# SCH___2021-06-06.net
KiCad netlist of a schematic drawn in EasyEDA
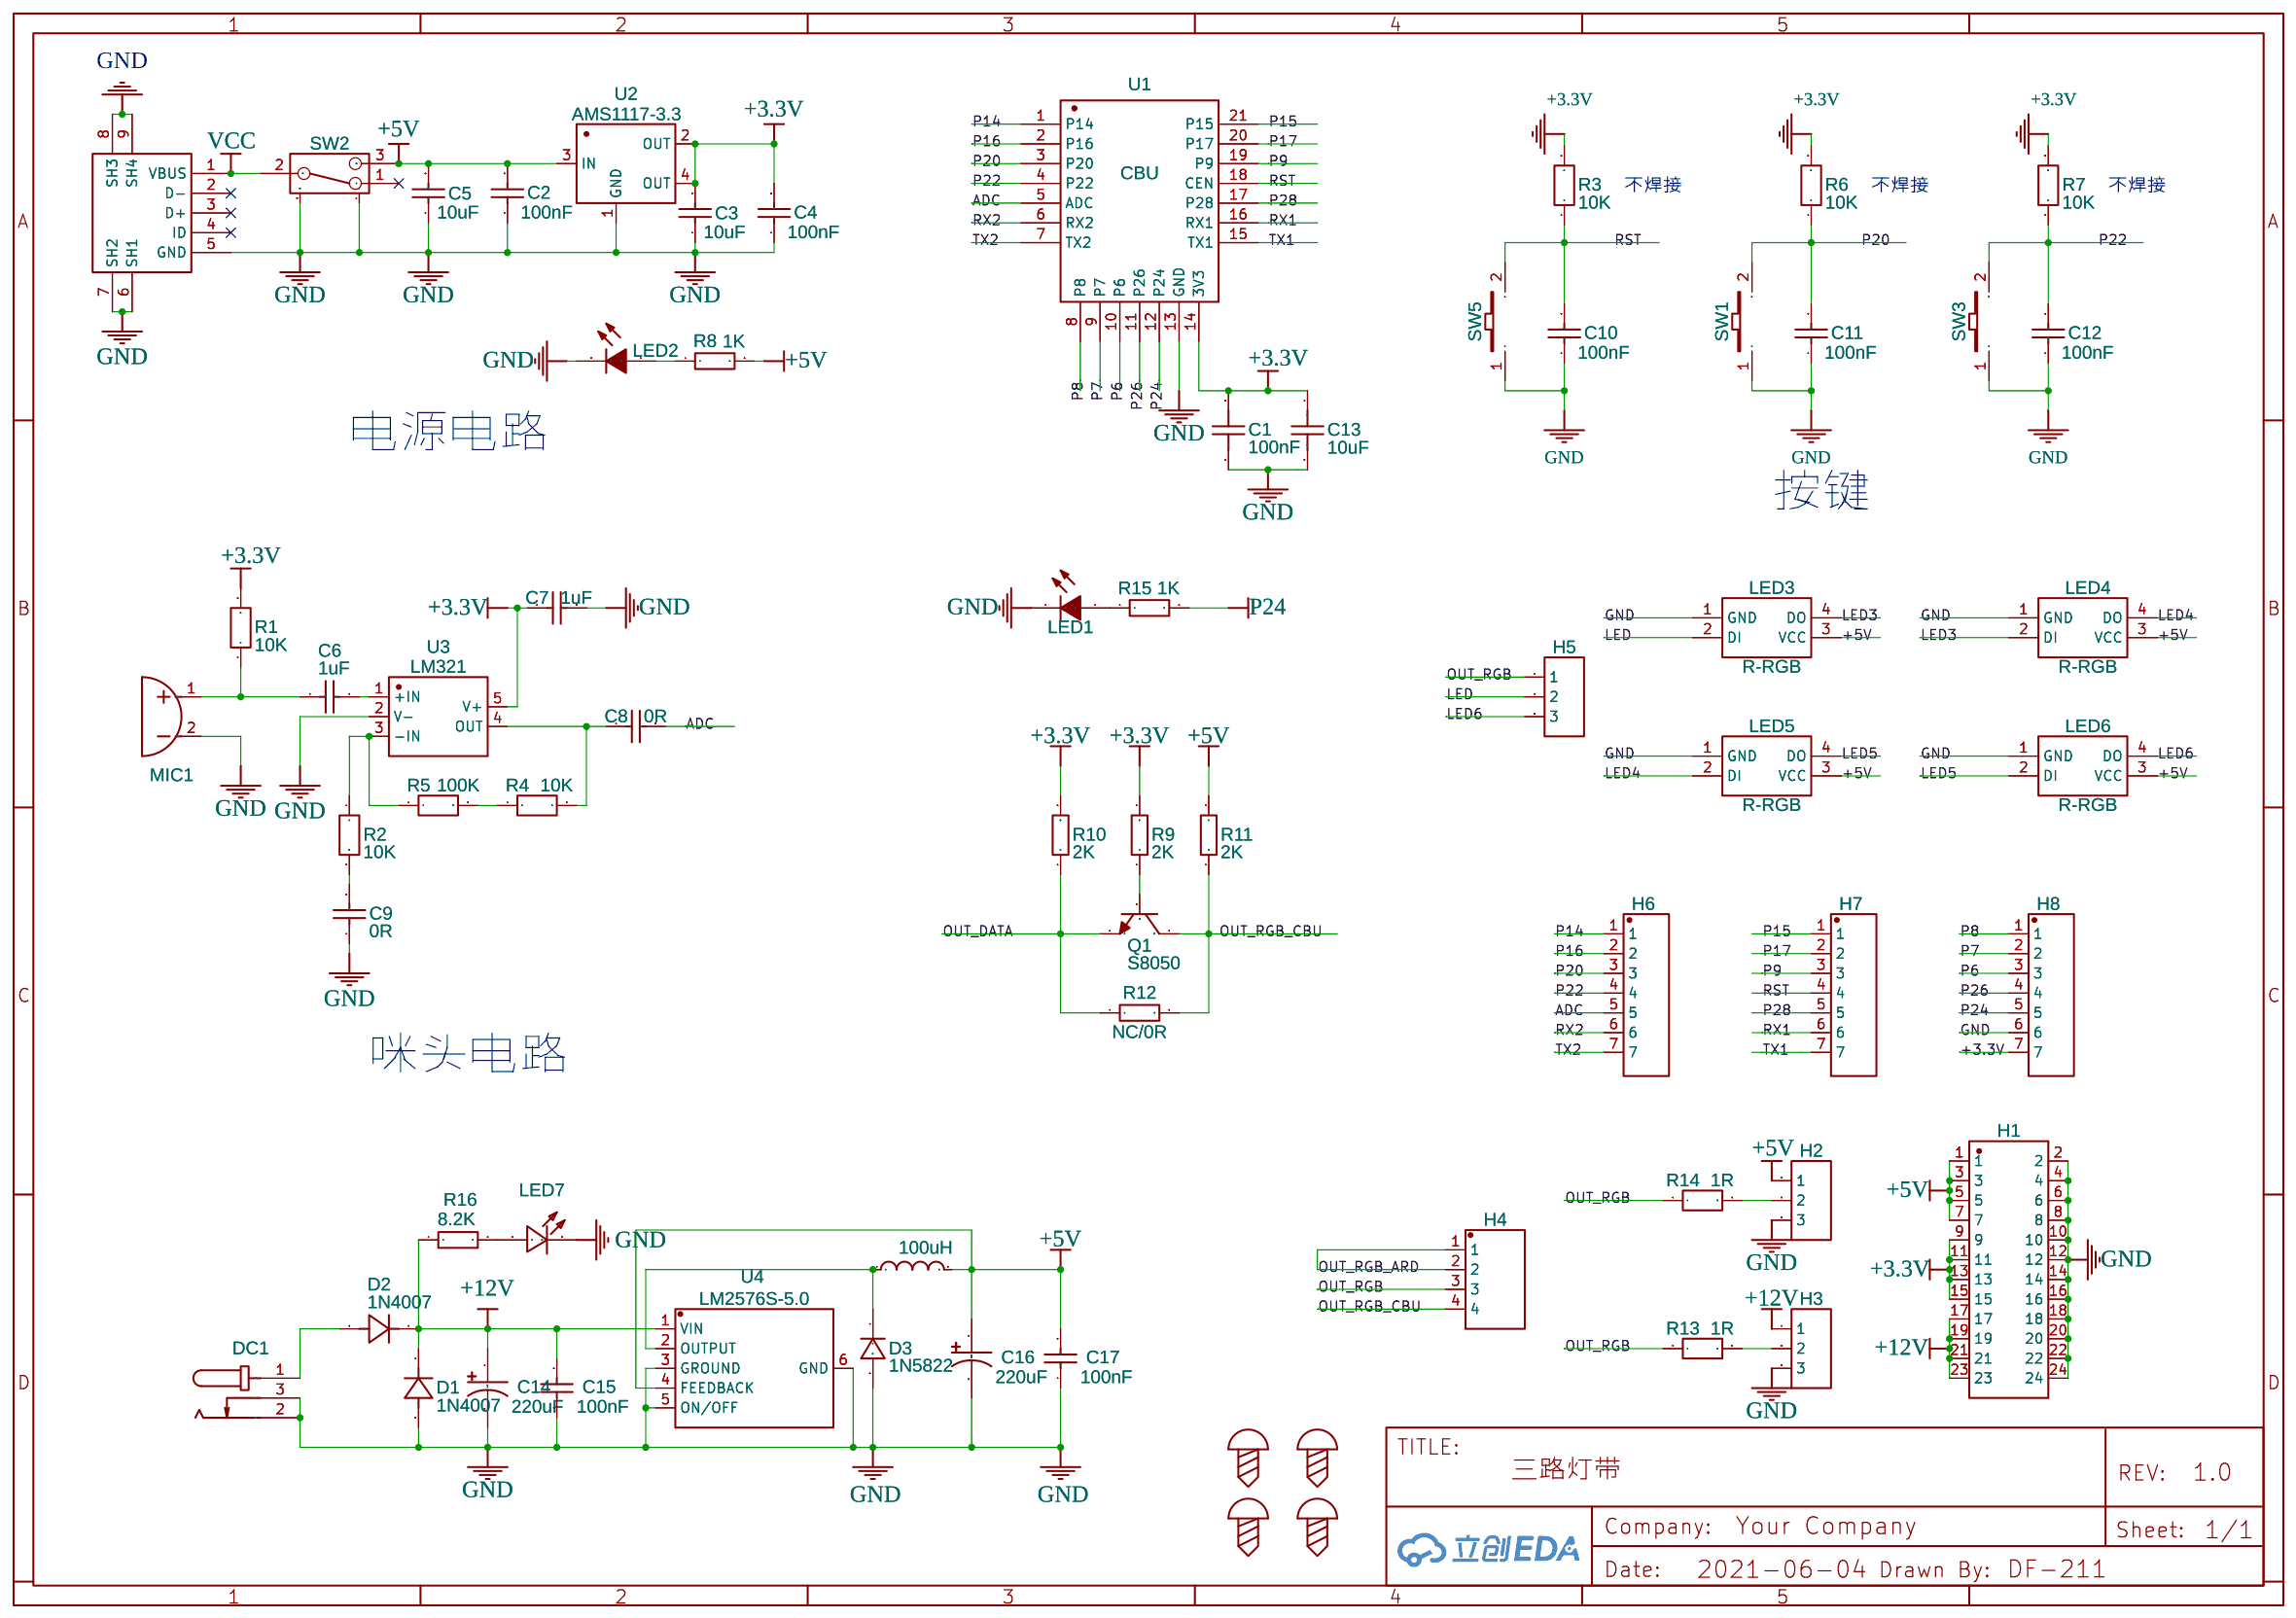
[diagram p0: 原理图]
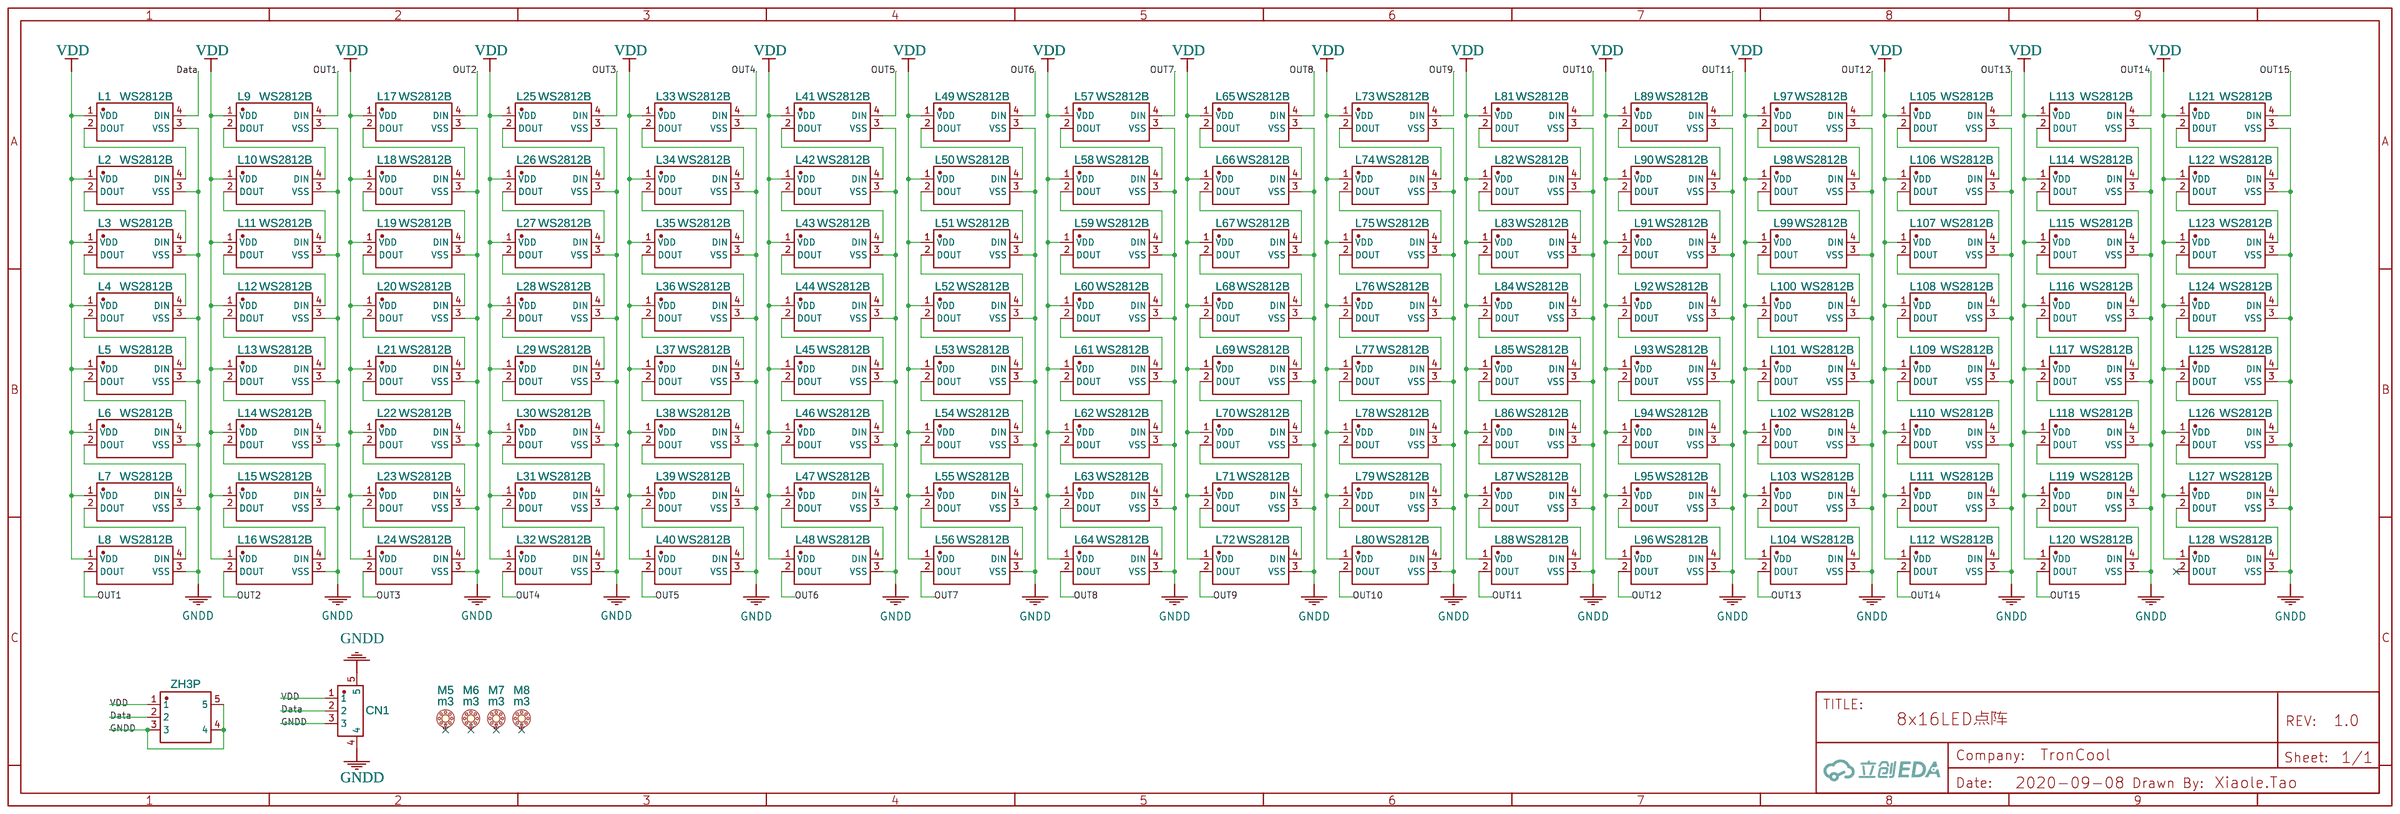
[diagram p1: WS2812灯带]

(export (version "E")
  (design (tool "Eeschema 10.0.6"))
  (components
    (comp (ref "C1")
      (value "100nF")
      (fields
        (field (name "BOM_Manufacturer Part") "CC0603KRX7R9BB104")
        (field (name "BOM_Supplier Part") "C14663")
      )
      (libsource (lib "") (part "CC0603KRX7R9BB104"))
    )
    (comp (ref "C2")
      (value "100nF")
      (fields
        (field (name "BOM_Manufacturer Part") "0805B104K500NT")
        (field (name "BOM_Supplier Part") "C38141")
      )
      (libsource (lib "") (part "0805B104K500NT"))
    )
    (comp (ref "C3")
      (value "10uF")
      (fields
        (field (name "BOM_Manufacturer Part") "CL21A106KOQNNNE")
        (field (name "BOM_Supplier Part") "C1713")
      )
      (libsource (lib "") (part "CL21A106KOQNNNE"))
    )
    (comp (ref "C4")
      (value "100nF")
      (fields
        (field (name "BOM_Manufacturer Part") "0805B104K500NT")
        (field (name "BOM_Supplier Part") "C38141")
      )
      (libsource (lib "") (part "0805B104K500NT"))
    )
    (comp (ref "C5")
      (value "10uF")
      (fields
        (field (name "BOM_Manufacturer Part") "CL21A106KOQNNNE")
        (field (name "BOM_Supplier Part") "C1713")
      )
      (libsource (lib "") (part "CL21A106KOQNNNE"))
    )
    (comp (ref "C6")
      (value "1uF")
      (fields
        (field (name "BOM_Manufacturer Part") "CL21F105ZAFNNNE")
        (field (name "BOM_Supplier Part") "C1761")
      )
      (libsource (lib "") (part "CL21F105ZAFNNNE"))
    )
    (comp (ref "C7")
      (value "1uF")
      (fields
        (field (name "BOM_Manufacturer Part") "CL21F105ZAFNNNE")
        (field (name "BOM_Supplier Part") "C1761")
      )
      (libsource (lib "") (part "CL21F105ZAFNNNE"))
    )
    (comp (ref "C8")
      (value "0R")
      (fields
        (field (name "BOM_Manufacturer Part") "CL21F105ZAFNNNE")
        (field (name "BOM_Supplier Part") "C1761")
      )
      (libsource (lib "") (part "CL21F105ZAFNNNE"))
    )
    (comp (ref "C9")
      (value "0R")
      (fields
        (field (name "BOM_Manufacturer Part") "CL21F105ZAFNNNE")
        (field (name "BOM_Supplier Part") "C1761")
      )
      (libsource (lib "") (part "CL21F105ZAFNNNE_1"))
    )
    (comp (ref "C10")
      (value "100nF")
      (fields
        (field (name "BOM_Manufacturer Part") "0805B104K500NT")
        (field (name "BOM_Supplier Part") "C38141")
      )
      (libsource (lib "") (part "0805B104K500NT"))
    )
    (comp (ref "C11")
      (value "100nF")
      (fields
        (field (name "BOM_Manufacturer Part") "0805B104K500NT")
        (field (name "BOM_Supplier Part") "C38141")
      )
      (libsource (lib "") (part "0805B104K500NT"))
    )
    (comp (ref "C12")
      (value "100nF")
      (fields
        (field (name "BOM_Manufacturer Part") "0805B104K500NT")
        (field (name "BOM_Supplier Part") "C38141")
      )
      (libsource (lib "") (part "0805B104K500NT"))
    )
    (comp (ref "C13")
      (value "10uF")
      (fields
        (field (name "BOM_Manufacturer Part") "JMK212AB7106KGHT")
        (field (name "BOM_Supplier Part") "C386019")
      )
      (libsource (lib "") (part "JMK212AB7106KGHT"))
    )
    (comp (ref "C14")
      (value "220uF")
      (fields
        (field (name "BOM_Manufacturer Part") "EEEFC1E221AP")
        (field (name "BOM_Supplier Part") "C178520")
      )
      (libsource (lib "") (part "EEEFC1E221AP"))
    )
    (comp (ref "C15")
      (value "100nF")
      (fields
        (field (name "BOM_Manufacturer Part") "CL21F104ZBCNNNC")
        (field (name "BOM_Supplier Part") "C1760")
      )
      (libsource (lib "") (part "CL21F104ZBCNNNC"))
    )
    (comp (ref "C16")
      (value "220uF")
      (fields
        (field (name "BOM_Manufacturer Part") "EEEFC1E221AP")
        (field (name "BOM_Supplier Part") "C178520")
      )
      (libsource (lib "") (part "EEEFC1E221AP_1"))
    )
    (comp (ref "C17")
      (value "100nF")
      (fields
        (field (name "BOM_Manufacturer Part") "CL10F104ZB8NNNC")
        (field (name "BOM_Supplier Part") "C1688")
      )
      (libsource (lib "") (part "CL10F104ZB8NNNC"))
    )
    (comp (ref "D1")
      (value "1N4007")
      (fields (field (name "BOM_Supplier Part") "C727081"))
      (libsource (lib "") (part "1N4007_C727081"))
    )
    (comp (ref "D2")
      (value "1N4007")
      (fields (field (name "BOM_Supplier Part") "C727081"))
      (libsource (lib "") (part "1N4007_C727081_1"))
    )
    (comp (ref "D3")
      (value "1N5822")
      (fields
        (field (name "BOM_Manufacturer Part") "SS36F-SMAF")
        (field (name "BOM_Supplier Part") "C364271")
      )
      (libsource (lib "") (part "1N5822-SMA"))
    )
    (comp (ref "DC1")
      (value "DC-005A-20A")
      (fields (field (name "BOM_Supplier Part") "C362144"))
      (libsource (lib "") (part "DC-005A-20A"))
    )
    (comp (ref "H1")
      (value "A2541HWV-2X12P")
      (fields
        (field (name "BOM_Manufacturer Part") "A2541HWV-2x12P")
        (field (name "BOM_Supplier Part") "C239352")
      )
      (libsource (lib "") (part "A2541HWV-2X12P"))
    )
    (comp (ref "H2")
      (value "Header-Male-2.54_1x3")
      (fields
        (field (name "BOM_Manufacturer Part") "Header2.54mm 1*3P")
        (field (name "BOM_Supplier Part") "C49257")
      )
      (libsource (lib "") (part "Header-Male-2.54_1x3"))
    )
    (comp (ref "H3")
      (value "Header-Male-2.54_1x3")
      (fields
        (field (name "BOM_Manufacturer Part") "Header2.54mm 1*3P")
        (field (name "BOM_Supplier Part") "C49257")
      )
      (libsource (lib "") (part "Header-Male-2.54_1x3"))
    )
    (comp (ref "H4")
      (value "MTP125-1104S1")
      (fields (field (name "BOM_Supplier Part") "C358686"))
      (libsource (lib "") (part "MTP125-1104S1"))
    )
    (comp (ref "H5")
      (value "Header-Male-2.54_1x3")
      (fields
        (field (name "BOM_Manufacturer Part") "Header2.54mm 1*3P")
        (field (name "BOM_Supplier Part") "C49257")
      )
      (libsource (lib "") (part "Header-Male-2.54_1x3"))
    )
    (comp (ref "H6")
      (value "220S-1*7P H=8.5MM Ytype Gold-plated")
      (fields (field (name "BOM_Supplier Part") "C124418"))
      (libsource (lib "") (part "220S-1*7P H=8.5MM Ytype Gold-plated"))
    )
    (comp (ref "H7")
      (value "220S-1*7P H=8.5MM Ytype Gold-plated")
      (fields (field (name "BOM_Supplier Part") "C124418"))
      (libsource (lib "") (part "220S-1*7P H=8.5MM Ytype Gold-plated"))
    )
    (comp (ref "H8")
      (value "220S-1*7P H=8.5MM Ytype Gold-plated")
      (fields (field (name "BOM_Supplier Part") "C124418"))
      (libsource (lib "") (part "220S-1*7P H=8.5MM Ytype Gold-plated"))
    )
    (comp (ref "LED1")
      (value "19-217/BHC-ZL1M2RY/3T")
      (fields (field (name "BOM_Supplier Part") "C72041"))
      (libsource (lib "") (part "19-217/BHC-ZL1M2RY/3T"))
    )
    (comp (ref "LED2")
      (value "19-217/BHC-ZL1M2RY/3T")
      (fields (field (name "BOM_Supplier Part") "C72041"))
      (libsource (lib "") (part "19-217/BHC-ZL1M2RY/3T"))
    )
    (comp (ref "LED3")
      (value "R-RGB")
      (fields (field (name "BOM_Manufacturer Part") "WS2812B-B") (field (name "BOM_Supplier Part") "C114586"))
      (libsource (lib "") (part "R-RGB"))
    )
    (comp (ref "LED4")
      (value "R-RGB")
      (fields (field (name "BOM_Manufacturer Part") "WS2812B-B") (field (name "BOM_Supplier Part") "C114586"))
      (libsource (lib "") (part "R-RGB"))
    )
    (comp (ref "LED5")
      (value "R-RGB")
      (fields (field (name "BOM_Manufacturer Part") "WS2812B-B") (field (name "BOM_Supplier Part") "C114586"))
      (libsource (lib "") (part "R-RGB"))
    )
    (comp (ref "LED6")
      (value "R-RGB")
      (fields (field (name "BOM_Manufacturer Part") "WS2812B-B") (field (name "BOM_Supplier Part") "C114586"))
      (libsource (lib "") (part "R-RGB"))
    )
    (comp (ref "LED7")
      (value "ORH-G35A")
      (fields (field (name "BOM_Supplier Part") "C205442"))
      (libsource (lib "") (part "ORH-G35A"))
    )
    (comp (ref "LL1")
      (value "100uH")
      (fields
        (field (name "BOM_Manufacturer Part") "GCRH125-101MC")
        (field (name "BOM_Supplier Part") "C439399")
      )
      (libsource (lib "") (part "GCRH125-101MC"))
    )
    (comp (ref "MIC1")
      (value "GMI9767P-36DB")
      (fields (field (name "BOM_Supplier Part") "C234015"))
      (libsource (lib "") (part "GMI9767P-36DB"))
    )
    (comp (ref "Q1")
      (value "S8050")
      (fields (field (name "BOM_Supplier Part") "C908252"))
      (libsource (lib "") (part "S8050_C908252"))
    )
    (comp (ref "R1")
      (value "10K")
      (fields
        (field (name "BOM_Manufacturer Part") "RT0805WRD0710KL")
        (field (name "BOM_Supplier Part") "C706400")
      )
      (libsource (lib "") (part "RT0805WRD0710KL"))
    )
    (comp (ref "R2")
      (value "10K")
      (fields
        (field (name "BOM_Manufacturer Part") "RT0805WRD0710KL")
        (field (name "BOM_Supplier Part") "C706400")
      )
      (libsource (lib "") (part "RT0805WRD0710KL_2"))
    )
    (comp (ref "R3")
      (value "10K")
      (fields
        (field (name "BOM_Manufacturer Part") "RT0805WRD0710KL")
        (field (name "BOM_Supplier Part") "C706400")
      )
      (libsource (lib "") (part "RT0805WRD0710KL"))
    )
    (comp (ref "R4")
      (value "10K")
      (fields
        (field (name "BOM_Manufacturer Part") "RT0805WRD0710KL")
        (field (name "BOM_Supplier Part") "C706400")
      )
      (libsource (lib "") (part "RT0805WRD0710KL_1"))
    )
    (comp (ref "R5")
      (value "100K")
      (fields
        (field (name "BOM_Manufacturer Part") "CRCW0805100KFKEA")
        (field (name "BOM_Supplier Part") "C844935")
      )
      (libsource (lib "") (part "CRCW0805100KFKEA"))
    )
    (comp (ref "R6")
      (value "10K")
      (fields
        (field (name "BOM_Manufacturer Part") "RT0805WRD0710KL")
        (field (name "BOM_Supplier Part") "C706400")
      )
      (libsource (lib "") (part "RT0805WRD0710KL"))
    )
    (comp (ref "R7")
      (value "10K")
      (fields
        (field (name "BOM_Manufacturer Part") "RT0805WRD0710KL")
        (field (name "BOM_Supplier Part") "C706400")
      )
      (libsource (lib "") (part "RT0805WRD0710KL"))
    )
    (comp (ref "R8")
      (value "1K")
      (fields
        (field (name "BOM_Manufacturer Part") "0805W8F1001T5E")
        (field (name "BOM_Supplier Part") "C17513")
      )
      (libsource (lib "") (part "0805W8F1001T5E"))
    )
    (comp (ref "R9")
      (value "2K")
      (fields
        (field (name "BOM_Manufacturer Part") "RMC08052K5%N")
        (field (name "BOM_Supplier Part") "C269731")
      )
      (libsource (lib "") (part "RMC08052K5%N"))
    )
    (comp (ref "R10")
      (value "2K")
      (fields
        (field (name "BOM_Manufacturer Part") "RMC08052K5%N")
        (field (name "BOM_Supplier Part") "C269731")
      )
      (libsource (lib "") (part "RMC08052K5%N"))
    )
    (comp (ref "R11")
      (value "2K")
      (fields
        (field (name "BOM_Manufacturer Part") "RMC08052K5%N")
        (field (name "BOM_Supplier Part") "C269731")
      )
      (libsource (lib "") (part "RMC08052K5%N"))
    )
    (comp (ref "R12")
      (value "NC/0R")
      (fields
        (field (name "BOM_Manufacturer Part") "0805W8J0000T5E")
        (field (name "BOM_Supplier Part") "C25275")
      )
      (libsource (lib "") (part "0805W8J0000T5E"))
    )
    (comp (ref "R13")
      (value "1R")
      (fields
        (field (name "BOM_Manufacturer Part") "AC0805DR-071RL")
        (field (name "BOM_Supplier Part") "C727972")
      )
      (libsource (lib "") (part "AC0805DR-071RL"))
    )
    (comp (ref "R14")
      (value "1R")
      (fields
        (field (name "BOM_Manufacturer Part") "AC0805DR-071RL")
        (field (name "BOM_Supplier Part") "C727972")
      )
      (libsource (lib "") (part "AC0805DR-071RL"))
    )
    (comp (ref "R15")
      (value "1K")
      (fields
        (field (name "BOM_Manufacturer Part") "0805W8F1001T5E")
        (field (name "BOM_Supplier Part") "C17513")
      )
      (libsource (lib "") (part "0805W8F1001T5E"))
    )
    (comp (ref "R16")
      (value "8.2K")
      (fields
        (field (name "BOM_Manufacturer Part") "0805W8J0822T5E")
        (field (name "BOM_Supplier Part") "C26028")
      )
      (libsource (lib "") (part "0805W8J0822T5E"))
    )
    (comp (ref "SW1")
      (value "S2")
      (fields
        (field (name "BOM_Manufacturer Part") "K2-1107ST-A4SW-06")
        (field (name "BOM_Supplier Part") "C118141")
      )
      (libsource (lib "") (part "Unknown_880_-650"))
    )
    (comp (ref "SW2")
      (value "SS-12D02-VG4")
      (fields (field (name "BOM_Supplier Part") "C136719"))
      (libsource (lib "") (part "SS-12D02-VG4"))
    )
    (comp (ref "SW3")
      (value "S2")
      (fields
        (field (name "BOM_Manufacturer Part") "K2-1107ST-A4SW-06")
        (field (name "BOM_Supplier Part") "C118141")
      )
      (libsource (lib "") (part "Unknown_1000_-650"))
    )
    (comp (ref "SW5")
      (value "S2")
      (fields
        (field (name "BOM_Manufacturer Part") "K2-1107ST-A4SW-06")
        (field (name "BOM_Supplier Part") "C118141")
      )
      (libsource (lib "") (part "Unknown_755_-650"))
    )
    (comp (ref "TP1") (value "M3铜柱") (libsource (lib "") (part "M3铜柱")))
    (comp (ref "TP2") (value "M3铜柱") (libsource (lib "") (part "M3铜柱")))
    (comp (ref "TP3") (value "M3铜柱") (libsource (lib "") (part "M3铜柱")))
    (comp (ref "TP4") (value "M3铜柱") (libsource (lib "") (part "M3铜柱")))
    (comp (ref "U1") (value "CBU") (libsource (lib "") (part "模块-CBU")))
    (comp (ref "U2")
      (value "AMS1117-3.3")
      (fields (field (name "BOM_Supplier Part") "C498117"))
      (libsource (lib "") (part "AMS1117-3.3"))
    )
    (comp (ref "U3")
      (value "LM321")
      (fields (field (name "BOM_Supplier Part") "C686636"))
      (libsource (lib "") (part "LM321"))
    )
    (comp (ref "U4")
      (value "LM2576S-5.0")
      (fields
        (field (name "BOM_Manufacturer Part") "LM2576S-5.0/TR")
        (field (name "BOM_Supplier Part") "C340927")
      )
      (libsource (lib "") (part "LM2576S-5.0/TR_C340927"))
    )
    (comp (ref "USB")
      (value "MICROXNJ")
      (fields (field (name "BOM_Manufacturer Part") "MicroXNJ") (field (name "BOM_Supplier Part") "C404969"))
      (libsource (lib "") (part "MICROXNJ"))
    )
    (comp (ref "CN1")
      (value "2.54-3P WT")
      (fields (field (name "BOM_Supplier Part") "C2681546"))
      (libsource (lib "") (part "2.54-3P WT"))
    )
    (comp (ref "CN6")
      (value "ZH3P")
      (fields (field (name "BOM_Supplier Part") "C145991"))
      (libsource (lib "") (part "ZH1.5-3P SMD"))
    )
    (comp (ref "L1")
      (value "WS2812B")
      (fields
        (field (name "BOM_Manufacturer Part") "WS2812B-Mini")
        (field (name "BOM_Supplier Part") "C527089")
      )
      (libsource (lib "") (part "WS2812B-MINI"))
    )
    (comp (ref "L2")
      (value "WS2812B")
      (fields
        (field (name "BOM_Manufacturer Part") "WS2812B-Mini")
        (field (name "BOM_Supplier Part") "C527089")
      )
      (libsource (lib "") (part "WS2812B-MINI"))
    )
    (comp (ref "L3")
      (value "WS2812B")
      (fields
        (field (name "BOM_Manufacturer Part") "WS2812B-Mini")
        (field (name "BOM_Supplier Part") "C527089")
      )
      (libsource (lib "") (part "WS2812B-MINI"))
    )
    (comp (ref "L4")
      (value "WS2812B")
      (fields
        (field (name "BOM_Manufacturer Part") "WS2812B-Mini")
        (field (name "BOM_Supplier Part") "C527089")
      )
      (libsource (lib "") (part "WS2812B-MINI"))
    )
    (comp (ref "L5")
      (value "WS2812B")
      (fields
        (field (name "BOM_Manufacturer Part") "WS2812B-Mini")
        (field (name "BOM_Supplier Part") "C527089")
      )
      (libsource (lib "") (part "WS2812B-MINI"))
    )
    (comp (ref "L6")
      (value "WS2812B")
      (fields
        (field (name "BOM_Manufacturer Part") "WS2812B-Mini")
        (field (name "BOM_Supplier Part") "C527089")
      )
      (libsource (lib "") (part "WS2812B-MINI"))
    )
    (comp (ref "L7")
      (value "WS2812B")
      (fields
        (field (name "BOM_Manufacturer Part") "WS2812B-Mini")
        (field (name "BOM_Supplier Part") "C527089")
      )
      (libsource (lib "") (part "WS2812B-MINI"))
    )
    (comp (ref "L8")
      (value "WS2812B")
      (fields
        (field (name "BOM_Manufacturer Part") "WS2812B-Mini")
        (field (name "BOM_Supplier Part") "C527089")
      )
      (libsource (lib "") (part "WS2812B-MINI"))
    )
    (comp (ref "L9")
      (value "WS2812B")
      (fields
        (field (name "BOM_Manufacturer Part") "WS2812B-Mini")
        (field (name "BOM_Supplier Part") "C527089")
      )
      (libsource (lib "") (part "WS2812B-MINI"))
    )
    (comp (ref "L10")
      (value "WS2812B")
      (fields
        (field (name "BOM_Manufacturer Part") "WS2812B-Mini")
        (field (name "BOM_Supplier Part") "C527089")
      )
      (libsource (lib "") (part "WS2812B-MINI"))
    )
    (comp (ref "L11")
      (value "WS2812B")
      (fields
        (field (name "BOM_Manufacturer Part") "WS2812B-Mini")
        (field (name "BOM_Supplier Part") "C527089")
      )
      (libsource (lib "") (part "WS2812B-MINI"))
    )
    (comp (ref "L12")
      (value "WS2812B")
      (fields
        (field (name "BOM_Manufacturer Part") "WS2812B-Mini")
        (field (name "BOM_Supplier Part") "C527089")
      )
      (libsource (lib "") (part "WS2812B-MINI"))
    )
    (comp (ref "L13")
      (value "WS2812B")
      (fields
        (field (name "BOM_Manufacturer Part") "WS2812B-Mini")
        (field (name "BOM_Supplier Part") "C527089")
      )
      (libsource (lib "") (part "WS2812B-MINI"))
    )
    (comp (ref "L14")
      (value "WS2812B")
      (fields
        (field (name "BOM_Manufacturer Part") "WS2812B-Mini")
        (field (name "BOM_Supplier Part") "C527089")
      )
      (libsource (lib "") (part "WS2812B-MINI"))
    )
    (comp (ref "L15")
      (value "WS2812B")
      (fields
        (field (name "BOM_Manufacturer Part") "WS2812B-Mini")
        (field (name "BOM_Supplier Part") "C527089")
      )
      (libsource (lib "") (part "WS2812B-MINI"))
    )
    (comp (ref "L16")
      (value "WS2812B")
      (fields
        (field (name "BOM_Manufacturer Part") "WS2812B-Mini")
        (field (name "BOM_Supplier Part") "C527089")
      )
      (libsource (lib "") (part "WS2812B-MINI"))
    )
    (comp (ref "L17")
      (value "WS2812B")
      (fields
        (field (name "BOM_Manufacturer Part") "WS2812B-Mini")
        (field (name "BOM_Supplier Part") "C527089")
      )
      (libsource (lib "") (part "WS2812B-MINI"))
    )
    (comp (ref "L18")
      (value "WS2812B")
      (fields
        (field (name "BOM_Manufacturer Part") "WS2812B-Mini")
        (field (name "BOM_Supplier Part") "C527089")
      )
      (libsource (lib "") (part "WS2812B-MINI"))
    )
    (comp (ref "L19")
      (value "WS2812B")
      (fields
        (field (name "BOM_Manufacturer Part") "WS2812B-Mini")
        (field (name "BOM_Supplier Part") "C527089")
      )
      (libsource (lib "") (part "WS2812B-MINI"))
    )
    (comp (ref "L20")
      (value "WS2812B")
      (fields
        (field (name "BOM_Manufacturer Part") "WS2812B-Mini")
        (field (name "BOM_Supplier Part") "C527089")
      )
      (libsource (lib "") (part "WS2812B-MINI"))
    )
    (comp (ref "L21")
      (value "WS2812B")
      (fields
        (field (name "BOM_Manufacturer Part") "WS2812B-Mini")
        (field (name "BOM_Supplier Part") "C527089")
      )
      (libsource (lib "") (part "WS2812B-MINI"))
    )
    (comp (ref "L22")
      (value "WS2812B")
      (fields
        (field (name "BOM_Manufacturer Part") "WS2812B-Mini")
        (field (name "BOM_Supplier Part") "C527089")
      )
      (libsource (lib "") (part "WS2812B-MINI"))
    )
    (comp (ref "L23")
      (value "WS2812B")
      (fields
        (field (name "BOM_Manufacturer Part") "WS2812B-Mini")
        (field (name "BOM_Supplier Part") "C527089")
      )
      (libsource (lib "") (part "WS2812B-MINI"))
    )
    (comp (ref "L24")
      (value "WS2812B")
      (fields
        (field (name "BOM_Manufacturer Part") "WS2812B-Mini")
        (field (name "BOM_Supplier Part") "C527089")
      )
      (libsource (lib "") (part "WS2812B-MINI"))
    )
    (comp (ref "L25")
      (value "WS2812B")
      (fields
        (field (name "BOM_Manufacturer Part") "WS2812B-Mini")
        (field (name "BOM_Supplier Part") "C527089")
      )
      (libsource (lib "") (part "WS2812B-MINI"))
    )
    (comp (ref "L26")
      (value "WS2812B")
      (fields
        (field (name "BOM_Manufacturer Part") "WS2812B-Mini")
        (field (name "BOM_Supplier Part") "C527089")
      )
      (libsource (lib "") (part "WS2812B-MINI"))
    )
    (comp (ref "L27")
      (value "WS2812B")
      (fields
        (field (name "BOM_Manufacturer Part") "WS2812B-Mini")
        (field (name "BOM_Supplier Part") "C527089")
      )
      (libsource (lib "") (part "WS2812B-MINI"))
    )
    (comp (ref "L28")
      (value "WS2812B")
      (fields
        (field (name "BOM_Manufacturer Part") "WS2812B-Mini")
        (field (name "BOM_Supplier Part") "C527089")
      )
      (libsource (lib "") (part "WS2812B-MINI"))
    )
    (comp (ref "L29")
      (value "WS2812B")
      (fields
        (field (name "BOM_Manufacturer Part") "WS2812B-Mini")
        (field (name "BOM_Supplier Part") "C527089")
      )
      (libsource (lib "") (part "WS2812B-MINI"))
    )
    (comp (ref "L30")
      (value "WS2812B")
      (fields
        (field (name "BOM_Manufacturer Part") "WS2812B-Mini")
        (field (name "BOM_Supplier Part") "C527089")
      )
      (libsource (lib "") (part "WS2812B-MINI"))
    )
    (comp (ref "L31")
      (value "WS2812B")
      (fields
        (field (name "BOM_Manufacturer Part") "WS2812B-Mini")
        (field (name "BOM_Supplier Part") "C527089")
      )
      (libsource (lib "") (part "WS2812B-MINI"))
    )
    (comp (ref "L32")
      (value "WS2812B")
      (fields
        (field (name "BOM_Manufacturer Part") "WS2812B-Mini")
        (field (name "BOM_Supplier Part") "C527089")
      )
      (libsource (lib "") (part "WS2812B-MINI"))
    )
    (comp (ref "L33")
      (value "WS2812B")
      (fields
        (field (name "BOM_Manufacturer Part") "WS2812B-Mini")
        (field (name "BOM_Supplier Part") "C527089")
      )
      (libsource (lib "") (part "WS2812B-MINI"))
    )
    (comp (ref "L34")
      (value "WS2812B")
      (fields
        (field (name "BOM_Manufacturer Part") "WS2812B-Mini")
        (field (name "BOM_Supplier Part") "C527089")
      )
      (libsource (lib "") (part "WS2812B-MINI"))
    )
    (comp (ref "L35")
      (value "WS2812B")
      (fields
        (field (name "BOM_Manufacturer Part") "WS2812B-Mini")
        (field (name "BOM_Supplier Part") "C527089")
      )
      (libsource (lib "") (part "WS2812B-MINI"))
    )
    (comp (ref "L36")
      (value "WS2812B")
      (fields
        (field (name "BOM_Manufacturer Part") "WS2812B-Mini")
        (field (name "BOM_Supplier Part") "C527089")
      )
      (libsource (lib "") (part "WS2812B-MINI"))
    )
    (comp (ref "L37")
      (value "WS2812B")
      (fields
        (field (name "BOM_Manufacturer Part") "WS2812B-Mini")
        (field (name "BOM_Supplier Part") "C527089")
      )
      (libsource (lib "") (part "WS2812B-MINI"))
    )
    (comp (ref "L38")
      (value "WS2812B")
      (fields
        (field (name "BOM_Manufacturer Part") "WS2812B-Mini")
        (field (name "BOM_Supplier Part") "C527089")
      )
      (libsource (lib "") (part "WS2812B-MINI"))
    )
    (comp (ref "L39")
      (value "WS2812B")
      (fields
        (field (name "BOM_Manufacturer Part") "WS2812B-Mini")
        (field (name "BOM_Supplier Part") "C527089")
      )
      (libsource (lib "") (part "WS2812B-MINI"))
    )
    (comp (ref "L40")
      (value "WS2812B")
      (fields
        (field (name "BOM_Manufacturer Part") "WS2812B-Mini")
        (field (name "BOM_Supplier Part") "C527089")
      )
      (libsource (lib "") (part "WS2812B-MINI"))
    )
    (comp (ref "L41")
      (value "WS2812B")
      (fields
        (field (name "BOM_Manufacturer Part") "WS2812B-Mini")
        (field (name "BOM_Supplier Part") "C527089")
      )
      (libsource (lib "") (part "WS2812B-MINI"))
    )
    (comp (ref "L42")
      (value "WS2812B")
      (fields
        (field (name "BOM_Manufacturer Part") "WS2812B-Mini")
        (field (name "BOM_Supplier Part") "C527089")
      )
      (libsource (lib "") (part "WS2812B-MINI"))
    )
    (comp (ref "L43")
      (value "WS2812B")
      (fields
        (field (name "BOM_Manufacturer Part") "WS2812B-Mini")
        (field (name "BOM_Supplier Part") "C527089")
      )
      (libsource (lib "") (part "WS2812B-MINI"))
    )
    (comp (ref "L44")
      (value "WS2812B")
      (fields
        (field (name "BOM_Manufacturer Part") "WS2812B-Mini")
        (field (name "BOM_Supplier Part") "C527089")
      )
      (libsource (lib "") (part "WS2812B-MINI"))
    )
    (comp (ref "L45")
      (value "WS2812B")
      (fields
        (field (name "BOM_Manufacturer Part") "WS2812B-Mini")
        (field (name "BOM_Supplier Part") "C527089")
      )
      (libsource (lib "") (part "WS2812B-MINI"))
    )
    (comp (ref "L46")
      (value "WS2812B")
      (fields
        (field (name "BOM_Manufacturer Part") "WS2812B-Mini")
        (field (name "BOM_Supplier Part") "C527089")
      )
      (libsource (lib "") (part "WS2812B-MINI"))
    )
    (comp (ref "L47")
      (value "WS2812B")
      (fields
        (field (name "BOM_Manufacturer Part") "WS2812B-Mini")
        (field (name "BOM_Supplier Part") "C527089")
      )
      (libsource (lib "") (part "WS2812B-MINI"))
    )
    (comp (ref "L48")
      (value "WS2812B")
      (fields
        (field (name "BOM_Manufacturer Part") "WS2812B-Mini")
        (field (name "BOM_Supplier Part") "C527089")
      )
      (libsource (lib "") (part "WS2812B-MINI"))
    )
    (comp (ref "L49")
      (value "WS2812B")
      (fields
        (field (name "BOM_Manufacturer Part") "WS2812B-Mini")
        (field (name "BOM_Supplier Part") "C527089")
      )
      (libsource (lib "") (part "WS2812B-MINI"))
    )
    (comp (ref "L50")
      (value "WS2812B")
      (fields
        (field (name "BOM_Manufacturer Part") "WS2812B-Mini")
        (field (name "BOM_Supplier Part") "C527089")
      )
      (libsource (lib "") (part "WS2812B-MINI"))
    )
    (comp (ref "L51")
      (value "WS2812B")
      (fields
        (field (name "BOM_Manufacturer Part") "WS2812B-Mini")
        (field (name "BOM_Supplier Part") "C527089")
      )
      (libsource (lib "") (part "WS2812B-MINI"))
    )
    (comp (ref "L52")
      (value "WS2812B")
      (fields
        (field (name "BOM_Manufacturer Part") "WS2812B-Mini")
        (field (name "BOM_Supplier Part") "C527089")
      )
      (libsource (lib "") (part "WS2812B-MINI"))
    )
    (comp (ref "L53")
      (value "WS2812B")
      (fields
        (field (name "BOM_Manufacturer Part") "WS2812B-Mini")
        (field (name "BOM_Supplier Part") "C527089")
      )
      (libsource (lib "") (part "WS2812B-MINI"))
    )
    (comp (ref "L54")
      (value "WS2812B")
      (fields
        (field (name "BOM_Manufacturer Part") "WS2812B-Mini")
        (field (name "BOM_Supplier Part") "C527089")
      )
      (libsource (lib "") (part "WS2812B-MINI"))
    )
    (comp (ref "L55")
      (value "WS2812B")
      (fields
        (field (name "BOM_Manufacturer Part") "WS2812B-Mini")
        (field (name "BOM_Supplier Part") "C527089")
      )
      (libsource (lib "") (part "WS2812B-MINI"))
    )
    (comp (ref "L56")
      (value "WS2812B")
      (fields
        (field (name "BOM_Manufacturer Part") "WS2812B-Mini")
        (field (name "BOM_Supplier Part") "C527089")
      )
      (libsource (lib "") (part "WS2812B-MINI"))
    )
    (comp (ref "L57")
      (value "WS2812B")
      (fields
        (field (name "BOM_Manufacturer Part") "WS2812B-Mini")
        (field (name "BOM_Supplier Part") "C527089")
      )
      (libsource (lib "") (part "WS2812B-MINI"))
    )
    (comp (ref "L58")
      (value "WS2812B")
      (fields
        (field (name "BOM_Manufacturer Part") "WS2812B-Mini")
        (field (name "BOM_Supplier Part") "C527089")
      )
      (libsource (lib "") (part "WS2812B-MINI"))
    )
    (comp (ref "L59")
      (value "WS2812B")
      (fields
        (field (name "BOM_Manufacturer Part") "WS2812B-Mini")
        (field (name "BOM_Supplier Part") "C527089")
      )
      (libsource (lib "") (part "WS2812B-MINI"))
    )
    (comp (ref "L60")
      (value "WS2812B")
      (fields
        (field (name "BOM_Manufacturer Part") "WS2812B-Mini")
        (field (name "BOM_Supplier Part") "C527089")
      )
      (libsource (lib "") (part "WS2812B-MINI"))
    )
    (comp (ref "L61")
      (value "WS2812B")
      (fields
        (field (name "BOM_Manufacturer Part") "WS2812B-Mini")
        (field (name "BOM_Supplier Part") "C527089")
      )
      (libsource (lib "") (part "WS2812B-MINI"))
    )
    (comp (ref "L62")
      (value "WS2812B")
      (fields
        (field (name "BOM_Manufacturer Part") "WS2812B-Mini")
        (field (name "BOM_Supplier Part") "C527089")
      )
      (libsource (lib "") (part "WS2812B-MINI"))
    )
    (comp (ref "L63")
      (value "WS2812B")
      (fields
        (field (name "BOM_Manufacturer Part") "WS2812B-Mini")
        (field (name "BOM_Supplier Part") "C527089")
      )
      (libsource (lib "") (part "WS2812B-MINI"))
    )
    (comp (ref "L64")
      (value "WS2812B")
      (fields
        (field (name "BOM_Manufacturer Part") "WS2812B-Mini")
        (field (name "BOM_Supplier Part") "C527089")
      )
      (libsource (lib "") (part "WS2812B-MINI"))
    )
    (comp (ref "L65")
      (value "WS2812B")
      (fields
        (field (name "BOM_Manufacturer Part") "WS2812B-Mini")
        (field (name "BOM_Supplier Part") "C527089")
      )
      (libsource (lib "") (part "WS2812B-MINI"))
    )
    (comp (ref "L66")
      (value "WS2812B")
      (fields
        (field (name "BOM_Manufacturer Part") "WS2812B-Mini")
        (field (name "BOM_Supplier Part") "C527089")
      )
      (libsource (lib "") (part "WS2812B-MINI"))
    )
    (comp (ref "L67")
      (value "WS2812B")
      (fields
        (field (name "BOM_Manufacturer Part") "WS2812B-Mini")
        (field (name "BOM_Supplier Part") "C527089")
      )
      (libsource (lib "") (part "WS2812B-MINI"))
    )
    (comp (ref "L68")
      (value "WS2812B")
      (fields
        (field (name "BOM_Manufacturer Part") "WS2812B-Mini")
        (field (name "BOM_Supplier Part") "C527089")
      )
      (libsource (lib "") (part "WS2812B-MINI"))
    )
    (comp (ref "L69")
      (value "WS2812B")
      (fields
        (field (name "BOM_Manufacturer Part") "WS2812B-Mini")
        (field (name "BOM_Supplier Part") "C527089")
      )
      (libsource (lib "") (part "WS2812B-MINI"))
    )
    (comp (ref "L70")
      (value "WS2812B")
      (fields
        (field (name "BOM_Manufacturer Part") "WS2812B-Mini")
        (field (name "BOM_Supplier Part") "C527089")
      )
      (libsource (lib "") (part "WS2812B-MINI"))
    )
    (comp (ref "L71")
      (value "WS2812B")
      (fields
        (field (name "BOM_Manufacturer Part") "WS2812B-Mini")
        (field (name "BOM_Supplier Part") "C527089")
      )
      (libsource (lib "") (part "WS2812B-MINI"))
    )
    (comp (ref "L72")
      (value "WS2812B")
      (fields
        (field (name "BOM_Manufacturer Part") "WS2812B-Mini")
        (field (name "BOM_Supplier Part") "C527089")
      )
      (libsource (lib "") (part "WS2812B-MINI"))
    )
    (comp (ref "L73")
      (value "WS2812B")
      (fields
        (field (name "BOM_Manufacturer Part") "WS2812B-Mini")
        (field (name "BOM_Supplier Part") "C527089")
      )
      (libsource (lib "") (part "WS2812B-MINI"))
    )
    (comp (ref "L74")
      (value "WS2812B")
      (fields
        (field (name "BOM_Manufacturer Part") "WS2812B-Mini")
        (field (name "BOM_Supplier Part") "C527089")
      )
      (libsource (lib "") (part "WS2812B-MINI"))
    )
    (comp (ref "L75")
      (value "WS2812B")
      (fields
        (field (name "BOM_Manufacturer Part") "WS2812B-Mini")
        (field (name "BOM_Supplier Part") "C527089")
      )
      (libsource (lib "") (part "WS2812B-MINI"))
    )
    (comp (ref "L76")
      (value "WS2812B")
      (fields
        (field (name "BOM_Manufacturer Part") "WS2812B-Mini")
        (field (name "BOM_Supplier Part") "C527089")
      )
      (libsource (lib "") (part "WS2812B-MINI"))
    )
    (comp (ref "L77")
      (value "WS2812B")
      (fields
        (field (name "BOM_Manufacturer Part") "WS2812B-Mini")
        (field (name "BOM_Supplier Part") "C527089")
      )
      (libsource (lib "") (part "WS2812B-MINI"))
    )
    (comp (ref "L78")
      (value "WS2812B")
      (fields
        (field (name "BOM_Manufacturer Part") "WS2812B-Mini")
        (field (name "BOM_Supplier Part") "C527089")
      )
      (libsource (lib "") (part "WS2812B-MINI"))
    )
    (comp (ref "L79")
      (value "WS2812B")
      (fields
        (field (name "BOM_Manufacturer Part") "WS2812B-Mini")
        (field (name "BOM_Supplier Part") "C527089")
      )
      (libsource (lib "") (part "WS2812B-MINI"))
    )
    (comp (ref "L80")
      (value "WS2812B")
      (fields
        (field (name "BOM_Manufacturer Part") "WS2812B-Mini")
        (field (name "BOM_Supplier Part") "C527089")
      )
      (libsource (lib "") (part "WS2812B-MINI"))
    )
    (comp (ref "L81")
      (value "WS2812B")
      (fields
        (field (name "BOM_Manufacturer Part") "WS2812B-Mini")
        (field (name "BOM_Supplier Part") "C527089")
      )
      (libsource (lib "") (part "WS2812B-MINI"))
    )
    (comp (ref "L82")
      (value "WS2812B")
      (fields
        (field (name "BOM_Manufacturer Part") "WS2812B-Mini")
        (field (name "BOM_Supplier Part") "C527089")
      )
      (libsource (lib "") (part "WS2812B-MINI"))
    )
    (comp (ref "L83")
      (value "WS2812B")
      (fields
        (field (name "BOM_Manufacturer Part") "WS2812B-Mini")
        (field (name "BOM_Supplier Part") "C527089")
      )
      (libsource (lib "") (part "WS2812B-MINI"))
    )
    (comp (ref "L84")
      (value "WS2812B")
      (fields
        (field (name "BOM_Manufacturer Part") "WS2812B-Mini")
        (field (name "BOM_Supplier Part") "C527089")
      )
      (libsource (lib "") (part "WS2812B-MINI"))
    )
    (comp (ref "L85")
      (value "WS2812B")
      (fields
        (field (name "BOM_Manufacturer Part") "WS2812B-Mini")
        (field (name "BOM_Supplier Part") "C527089")
      )
      (libsource (lib "") (part "WS2812B-MINI"))
    )
    (comp (ref "L86")
      (value "WS2812B")
      (fields
        (field (name "BOM_Manufacturer Part") "WS2812B-Mini")
        (field (name "BOM_Supplier Part") "C527089")
      )
      (libsource (lib "") (part "WS2812B-MINI"))
    )
    (comp (ref "L87")
      (value "WS2812B")
      (fields
        (field (name "BOM_Manufacturer Part") "WS2812B-Mini")
        (field (name "BOM_Supplier Part") "C527089")
      )
      (libsource (lib "") (part "WS2812B-MINI"))
    )
    (comp (ref "L88")
      (value "WS2812B")
      (fields
        (field (name "BOM_Manufacturer Part") "WS2812B-Mini")
        (field (name "BOM_Supplier Part") "C527089")
      )
      (libsource (lib "") (part "WS2812B-MINI"))
    )
    (comp (ref "L89")
      (value "WS2812B")
      (fields
        (field (name "BOM_Manufacturer Part") "WS2812B-Mini")
        (field (name "BOM_Supplier Part") "C527089")
      )
      (libsource (lib "") (part "WS2812B-MINI"))
    )
    (comp (ref "L90")
      (value "WS2812B")
      (fields
        (field (name "BOM_Manufacturer Part") "WS2812B-Mini")
        (field (name "BOM_Supplier Part") "C527089")
      )
      (libsource (lib "") (part "WS2812B-MINI"))
    )
    (comp (ref "L91")
      (value "WS2812B")
      (fields
        (field (name "BOM_Manufacturer Part") "WS2812B-Mini")
        (field (name "BOM_Supplier Part") "C527089")
      )
      (libsource (lib "") (part "WS2812B-MINI"))
    )
    (comp (ref "L92")
      (value "WS2812B")
      (fields
        (field (name "BOM_Manufacturer Part") "WS2812B-Mini")
        (field (name "BOM_Supplier Part") "C527089")
      )
      (libsource (lib "") (part "WS2812B-MINI"))
    )
    (comp (ref "L93")
      (value "WS2812B")
      (fields
        (field (name "BOM_Manufacturer Part") "WS2812B-Mini")
        (field (name "BOM_Supplier Part") "C527089")
      )
      (libsource (lib "") (part "WS2812B-MINI"))
    )
    (comp (ref "L94")
      (value "WS2812B")
      (fields
        (field (name "BOM_Manufacturer Part") "WS2812B-Mini")
        (field (name "BOM_Supplier Part") "C527089")
      )
      (libsource (lib "") (part "WS2812B-MINI"))
    )
    (comp (ref "L95")
      (value "WS2812B")
      (fields
        (field (name "BOM_Manufacturer Part") "WS2812B-Mini")
        (field (name "BOM_Supplier Part") "C527089")
      )
      (libsource (lib "") (part "WS2812B-MINI"))
    )
    (comp (ref "L96")
      (value "WS2812B")
      (fields
        (field (name "BOM_Manufacturer Part") "WS2812B-Mini")
        (field (name "BOM_Supplier Part") "C527089")
      )
      (libsource (lib "") (part "WS2812B-MINI"))
    )
    (comp (ref "L97")
      (value "WS2812B")
      (fields
        (field (name "BOM_Manufacturer Part") "WS2812B-Mini")
        (field (name "BOM_Supplier Part") "C527089")
      )
      (libsource (lib "") (part "WS2812B-MINI"))
    )
    (comp (ref "L98")
      (value "WS2812B")
      (fields
        (field (name "BOM_Manufacturer Part") "WS2812B-Mini")
        (field (name "BOM_Supplier Part") "C527089")
      )
      (libsource (lib "") (part "WS2812B-MINI"))
    )
    (comp (ref "L99")
      (value "WS2812B")
      (fields
        (field (name "BOM_Manufacturer Part") "WS2812B-Mini")
        (field (name "BOM_Supplier Part") "C527089")
      )
      (libsource (lib "") (part "WS2812B-MINI"))
    )
    (comp (ref "L100")
      (value "WS2812B")
      (fields
        (field (name "BOM_Manufacturer Part") "WS2812B-Mini")
        (field (name "BOM_Supplier Part") "C527089")
      )
      (libsource (lib "") (part "WS2812B-MINI"))
    )
    (comp (ref "L101")
      (value "WS2812B")
      (fields
        (field (name "BOM_Manufacturer Part") "WS2812B-Mini")
        (field (name "BOM_Supplier Part") "C527089")
      )
      (libsource (lib "") (part "WS2812B-MINI"))
    )
    (comp (ref "L102")
      (value "WS2812B")
      (fields
        (field (name "BOM_Manufacturer Part") "WS2812B-Mini")
        (field (name "BOM_Supplier Part") "C527089")
      )
      (libsource (lib "") (part "WS2812B-MINI"))
    )
    (comp (ref "L103")
      (value "WS2812B")
      (fields
        (field (name "BOM_Manufacturer Part") "WS2812B-Mini")
        (field (name "BOM_Supplier Part") "C527089")
      )
      (libsource (lib "") (part "WS2812B-MINI"))
    )
    (comp (ref "L104")
      (value "WS2812B")
      (fields
        (field (name "BOM_Manufacturer Part") "WS2812B-Mini")
        (field (name "BOM_Supplier Part") "C527089")
      )
      (libsource (lib "") (part "WS2812B-MINI"))
    )
    (comp (ref "L105")
      (value "WS2812B")
      (fields
        (field (name "BOM_Manufacturer Part") "WS2812B-Mini")
        (field (name "BOM_Supplier Part") "C527089")
      )
      (libsource (lib "") (part "WS2812B-MINI"))
    )
    (comp (ref "L106")
      (value "WS2812B")
      (fields
        (field (name "BOM_Manufacturer Part") "WS2812B-Mini")
        (field (name "BOM_Supplier Part") "C527089")
      )
      (libsource (lib "") (part "WS2812B-MINI"))
    )
    (comp (ref "L107")
      (value "WS2812B")
      (fields
        (field (name "BOM_Manufacturer Part") "WS2812B-Mini")
        (field (name "BOM_Supplier Part") "C527089")
      )
      (libsource (lib "") (part "WS2812B-MINI"))
    )
    (comp (ref "L108")
      (value "WS2812B")
      (fields
        (field (name "BOM_Manufacturer Part") "WS2812B-Mini")
        (field (name "BOM_Supplier Part") "C527089")
      )
      (libsource (lib "") (part "WS2812B-MINI"))
    )
    (comp (ref "L109")
      (value "WS2812B")
      (fields
        (field (name "BOM_Manufacturer Part") "WS2812B-Mini")
        (field (name "BOM_Supplier Part") "C527089")
      )
      (libsource (lib "") (part "WS2812B-MINI"))
    )
    (comp (ref "L110")
      (value "WS2812B")
      (fields
        (field (name "BOM_Manufacturer Part") "WS2812B-Mini")
        (field (name "BOM_Supplier Part") "C527089")
      )
      (libsource (lib "") (part "WS2812B-MINI"))
    )
    (comp (ref "L111")
      (value "WS2812B")
      (fields
        (field (name "BOM_Manufacturer Part") "WS2812B-Mini")
        (field (name "BOM_Supplier Part") "C527089")
      )
      (libsource (lib "") (part "WS2812B-MINI"))
    )
    (comp (ref "L112")
      (value "WS2812B")
      (fields
        (field (name "BOM_Manufacturer Part") "WS2812B-Mini")
        (field (name "BOM_Supplier Part") "C527089")
      )
      (libsource (lib "") (part "WS2812B-MINI"))
    )
    (comp (ref "L113")
      (value "WS2812B")
      (fields
        (field (name "BOM_Manufacturer Part") "WS2812B-Mini")
        (field (name "BOM_Supplier Part") "C527089")
      )
      (libsource (lib "") (part "WS2812B-MINI"))
    )
    (comp (ref "L114")
      (value "WS2812B")
      (fields
        (field (name "BOM_Manufacturer Part") "WS2812B-Mini")
        (field (name "BOM_Supplier Part") "C527089")
      )
      (libsource (lib "") (part "WS2812B-MINI"))
    )
    (comp (ref "L115")
      (value "WS2812B")
      (fields
        (field (name "BOM_Manufacturer Part") "WS2812B-Mini")
        (field (name "BOM_Supplier Part") "C527089")
      )
      (libsource (lib "") (part "WS2812B-MINI"))
    )
    (comp (ref "L116")
      (value "WS2812B")
      (fields
        (field (name "BOM_Manufacturer Part") "WS2812B-Mini")
        (field (name "BOM_Supplier Part") "C527089")
      )
      (libsource (lib "") (part "WS2812B-MINI"))
    )
    (comp (ref "L117")
      (value "WS2812B")
      (fields
        (field (name "BOM_Manufacturer Part") "WS2812B-Mini")
        (field (name "BOM_Supplier Part") "C527089")
      )
      (libsource (lib "") (part "WS2812B-MINI"))
    )
    (comp (ref "L118")
      (value "WS2812B")
      (fields
        (field (name "BOM_Manufacturer Part") "WS2812B-Mini")
        (field (name "BOM_Supplier Part") "C527089")
      )
      (libsource (lib "") (part "WS2812B-MINI"))
    )
    (comp (ref "L119")
      (value "WS2812B")
      (fields
        (field (name "BOM_Manufacturer Part") "WS2812B-Mini")
        (field (name "BOM_Supplier Part") "C527089")
      )
      (libsource (lib "") (part "WS2812B-MINI"))
    )
    (comp (ref "L120")
      (value "WS2812B")
      (fields
        (field (name "BOM_Manufacturer Part") "WS2812B-Mini")
        (field (name "BOM_Supplier Part") "C527089")
      )
      (libsource (lib "") (part "WS2812B-MINI"))
    )
    (comp (ref "L121")
      (value "WS2812B")
      (fields
        (field (name "BOM_Manufacturer Part") "WS2812B-Mini")
        (field (name "BOM_Supplier Part") "C527089")
      )
      (libsource (lib "") (part "WS2812B-MINI"))
    )
    (comp (ref "L122")
      (value "WS2812B")
      (fields
        (field (name "BOM_Manufacturer Part") "WS2812B-Mini")
        (field (name "BOM_Supplier Part") "C527089")
      )
      (libsource (lib "") (part "WS2812B-MINI"))
    )
    (comp (ref "L123")
      (value "WS2812B")
      (fields
        (field (name "BOM_Manufacturer Part") "WS2812B-Mini")
        (field (name "BOM_Supplier Part") "C527089")
      )
      (libsource (lib "") (part "WS2812B-MINI"))
    )
    (comp (ref "L124")
      (value "WS2812B")
      (fields
        (field (name "BOM_Manufacturer Part") "WS2812B-Mini")
        (field (name "BOM_Supplier Part") "C527089")
      )
      (libsource (lib "") (part "WS2812B-MINI"))
    )
    (comp (ref "L125")
      (value "WS2812B")
      (fields
        (field (name "BOM_Manufacturer Part") "WS2812B-Mini")
        (field (name "BOM_Supplier Part") "C527089")
      )
      (libsource (lib "") (part "WS2812B-MINI"))
    )
    (comp (ref "L126")
      (value "WS2812B")
      (fields
        (field (name "BOM_Manufacturer Part") "WS2812B-Mini")
        (field (name "BOM_Supplier Part") "C527089")
      )
      (libsource (lib "") (part "WS2812B-MINI"))
    )
    (comp (ref "L127")
      (value "WS2812B")
      (fields
        (field (name "BOM_Manufacturer Part") "WS2812B-Mini")
        (field (name "BOM_Supplier Part") "C527089")
      )
      (libsource (lib "") (part "WS2812B-MINI"))
    )
    (comp (ref "L128")
      (value "WS2812B")
      (fields
        (field (name "BOM_Manufacturer Part") "WS2812B-Mini")
        (field (name "BOM_Supplier Part") "C527089")
      )
      (libsource (lib "") (part "WS2812B-MINI"))
    )
    (comp (ref "M5") (value "m3") (libsource (lib "") (part "m3")))
    (comp (ref "M6") (value "m3") (libsource (lib "") (part "m3")))
    (comp (ref "M7") (value "m3") (libsource (lib "") (part "m3")))
    (comp (ref "M8") (value "m3") (libsource (lib "") (part "m3")))
  )
  (nets
    (net (code "1") (name "+3.3V") (class "Default")
      (node (ref "C1") (pin "2") (pinfunction "2_2") (pintype "unspecified"))
      (node (ref "C13") (pin "1") (pinfunction "1_1") (pintype "unspecified"))
      (node (ref "C3") (pin "2") (pinfunction "2_2") (pintype "input"))
      (node (ref "C4") (pin "2") (pinfunction "2_2") (pintype "input"))
      (node (ref "C7") (pin "1") (pinfunction "1_1") (pintype "input"))
      (node (ref "H1") (pin "11") (pinfunction "11_11") (pintype "unspecified"))
      (node (ref "H1") (pin "13") (pinfunction "13_13") (pintype "unspecified"))
      (node (ref "H1") (pin "15") (pinfunction "15_15") (pintype "unspecified"))
      (node (ref "H1") (pin "9") (pinfunction "9_9") (pintype "unspecified"))
      (node (ref "H8") (pin "7") (pinfunction "7_7") (pintype "unspecified"))
      (node (ref "R1") (pin "2") (pinfunction "2_2") (pintype "unspecified"))
      (node (ref "R10") (pin "2") (pinfunction "2_2") (pintype "unspecified"))
      (node (ref "R3") (pin "2") (pinfunction "2_2") (pintype "unspecified"))
      (node (ref "R6") (pin "2") (pinfunction "2_2") (pintype "unspecified"))
      (node (ref "R7") (pin "2") (pinfunction "2_2") (pintype "unspecified"))
      (node (ref "R9") (pin "2") (pinfunction "2_2") (pintype "unspecified"))
      (node (ref "U1") (pin "14") (pinfunction "3V3_14") (pintype "unspecified"))
      (node (ref "U2") (pin "2") (pinfunction "OUT_2") (pintype "unspecified"))
      (node (ref "U2") (pin "4") (pinfunction "OUT_4") (pintype "unspecified"))
      (node (ref "U3") (pin "5") (pinfunction "V+_5") (pintype "unspecified"))
    )
    (net (code "2") (name "+5V") (class "Default")
      (node (ref "C16") (pin "1") (pinfunction "1_1") (pintype "unspecified"))
      (node (ref "C17") (pin "2") (pinfunction "2_2") (pintype "input"))
      (node (ref "C2") (pin "2") (pinfunction "2_2") (pintype "input"))
      (node (ref "C5") (pin "2") (pinfunction "2_2") (pintype "input"))
      (node (ref "H1") (pin "1") (pinfunction "1_1") (pintype "unspecified"))
      (node (ref "H1") (pin "3") (pinfunction "3_3") (pintype "unspecified"))
      (node (ref "H1") (pin "5") (pinfunction "5_5") (pintype "unspecified"))
      (node (ref "H1") (pin "7") (pinfunction "7_7") (pintype "unspecified"))
      (node (ref "H2") (pin "1") (pinfunction "1_1") (pintype "input"))
      (node (ref "LED3") (pin "3") (pinfunction "VCC_3") (pintype "unspecified"))
      (node (ref "LED4") (pin "3") (pinfunction "VCC_3") (pintype "unspecified"))
      (node (ref "LED5") (pin "3") (pinfunction "VCC_3") (pintype "unspecified"))
      (node (ref "LED6") (pin "3") (pinfunction "VCC_3") (pintype "unspecified"))
      (node (ref "LL1") (pin "2") (pinfunction "2_2") (pintype "unspecified"))
      (node (ref "R11") (pin "2") (pinfunction "2_2") (pintype "unspecified"))
      (node (ref "R8") (pin "2") (pinfunction "2_2") (pintype "input"))
      (node (ref "SW2") (pin "3") (pinfunction "3_3") (pintype "unspecified"))
      (node (ref "U2") (pin "3") (pinfunction "IN_3") (pintype "unspecified"))
      (node (ref "U4") (pin "4") (pinfunction "FEEDBACK_4") (pintype "unspecified"))
    )
    (net (code "3") (name "+12V") (class "Default")
      (node (ref "C14") (pin "1") (pinfunction "1_1") (pintype "unspecified"))
      (node (ref "C15") (pin "2") (pinfunction "2_2") (pintype "input"))
      (node (ref "D1") (pin "1") (pinfunction "K_1") (pintype "unspecified"))
      (node (ref "D2") (pin "1") (pinfunction "K_1") (pintype "unspecified"))
      (node (ref "H1") (pin "17") (pinfunction "17_17") (pintype "unspecified"))
      (node (ref "H1") (pin "19") (pinfunction "19_19") (pintype "unspecified"))
      (node (ref "H1") (pin "21") (pinfunction "21_21") (pintype "unspecified"))
      (node (ref "H1") (pin "23") (pinfunction "23_23") (pintype "unspecified"))
      (node (ref "H3") (pin "1") (pinfunction "1_1") (pintype "input"))
      (node (ref "R16") (pin "1") (pinfunction "1_1") (pintype "input"))
      (node (ref "U4") (pin "1") (pinfunction "VIN_1") (pintype "unspecified"))
    )
    (net (code "4") (name "ADC") (class "Default")
      (node (ref "C8") (pin "2") (pinfunction "2_2") (pintype "input"))
      (node (ref "H6") (pin "5") (pinfunction "5_5") (pintype "unspecified"))
      (node (ref "U1") (pin "5") (pinfunction "ADC_5") (pintype "unspecified"))
    )
    (net (code "5") (name "Data") (class "Default")
      (node (ref "CN1") (pin "2") (pinfunction "2_2") (pintype "unspecified"))
      (node (ref "CN6") (pin "2") (pinfunction "2_2") (pintype "unspecified"))
      (node (ref "L1") (pin "4") (pinfunction "DIN_4") (pintype "unspecified"))
    )
    (net (code "6") (name "GND") (class "Default")
      (node (ref "C1") (pin "1") (pinfunction "1_1") (pintype "unspecified"))
      (node (ref "C10") (pin "1") (pinfunction "1_1") (pintype "input"))
      (node (ref "C11") (pin "1") (pinfunction "1_1") (pintype "input"))
      (node (ref "C12") (pin "1") (pinfunction "1_1") (pintype "input"))
      (node (ref "C13") (pin "2") (pinfunction "2_2") (pintype "unspecified"))
      (node (ref "C14") (pin "2") (pinfunction "2_2") (pintype "unspecified"))
      (node (ref "C15") (pin "1") (pinfunction "1_1") (pintype "input"))
      (node (ref "C16") (pin "2") (pinfunction "2_2") (pintype "unspecified"))
      (node (ref "C17") (pin "1") (pinfunction "1_1") (pintype "input"))
      (node (ref "C2") (pin "1") (pinfunction "1_1") (pintype "input"))
      (node (ref "C3") (pin "1") (pinfunction "1_1") (pintype "input"))
      (node (ref "C4") (pin "1") (pinfunction "1_1") (pintype "input"))
      (node (ref "C5") (pin "1") (pinfunction "1_1") (pintype "input"))
      (node (ref "C7") (pin "2") (pinfunction "2_2") (pintype "input"))
      (node (ref "C9") (pin "1") (pinfunction "1_1") (pintype "input"))
      (node (ref "D1") (pin "2") (pinfunction "A_2") (pintype "unspecified"))
      (node (ref "D3") (pin "2") (pinfunction "2_2") (pintype "unspecified"))
      (node (ref "DC1") (pin "2") (pinfunction "2_2") (pintype "unspecified"))
      (node (ref "DC1") (pin "3") (pinfunction "3_3") (pintype "unspecified"))
      (node (ref "H1") (pin "10") (pinfunction "10_10") (pintype "unspecified"))
      (node (ref "H1") (pin "12") (pinfunction "12_12") (pintype "unspecified"))
      (node (ref "H1") (pin "14") (pinfunction "14_14") (pintype "unspecified"))
      (node (ref "H1") (pin "16") (pinfunction "16_16") (pintype "unspecified"))
      (node (ref "H1") (pin "18") (pinfunction "18_18") (pintype "unspecified"))
      (node (ref "H1") (pin "2") (pinfunction "2_2") (pintype "unspecified"))
      (node (ref "H1") (pin "20") (pinfunction "20_20") (pintype "unspecified"))
      (node (ref "H1") (pin "22") (pinfunction "22_22") (pintype "unspecified"))
      (node (ref "H1") (pin "24") (pinfunction "24_24") (pintype "unspecified"))
      (node (ref "H1") (pin "4") (pinfunction "4_4") (pintype "unspecified"))
      (node (ref "H1") (pin "6") (pinfunction "6_6") (pintype "unspecified"))
      (node (ref "H1") (pin "8") (pinfunction "8_8") (pintype "unspecified"))
      (node (ref "H2") (pin "3") (pinfunction "3_3") (pintype "input"))
      (node (ref "H3") (pin "3") (pinfunction "3_3") (pintype "input"))
      (node (ref "H8") (pin "6") (pinfunction "6_6") (pintype "unspecified"))
      (node (ref "LED1") (pin "2") (pinfunction "C_2") (pintype "input"))
      (node (ref "LED2") (pin "2") (pinfunction "C_2") (pintype "input"))
      (node (ref "LED3") (pin "1") (pinfunction "GND_1") (pintype "unspecified"))
      (node (ref "LED4") (pin "1") (pinfunction "GND_1") (pintype "unspecified"))
      (node (ref "LED5") (pin "1") (pinfunction "GND_1") (pintype "unspecified"))
      (node (ref "LED6") (pin "1") (pinfunction "GND_1") (pintype "unspecified"))
      (node (ref "LED7") (pin "2") (pinfunction "C_2") (pintype "unspecified"))
      (node (ref "MIC1") (pin "2") (pinfunction "2_2") (pintype "unspecified"))
      (node (ref "SW1") (pin "1") (pinfunction "1_1") (pintype "input"))
      (node (ref "SW2") (pin "4") (pinfunction "4_4") (pintype "unspecified"))
      (node (ref "SW2") (pin "5") (pinfunction "5_5") (pintype "unspecified"))
      (node (ref "SW3") (pin "1") (pinfunction "1_1") (pintype "input"))
      (node (ref "SW5") (pin "1") (pinfunction "1_1") (pintype "input"))
      (node (ref "U1") (pin "13") (pinfunction "GND_13") (pintype "unspecified"))
      (node (ref "U2") (pin "1") (pinfunction "GND_1") (pintype "unspecified"))
      (node (ref "U3") (pin "2") (pinfunction "V-_2") (pintype "unspecified"))
      (node (ref "U4") (pin "3") (pinfunction "GROUND_3") (pintype "unspecified"))
      (node (ref "U4") (pin "5") (pinfunction "ON/OFF_5") (pintype "unspecified"))
      (node (ref "U4") (pin "6") (pinfunction "GND_6") (pintype "unspecified"))
      (node (ref "USB") (pin "5") (pinfunction "GND_5") (pintype "unspecified"))
      (node (ref "USB") (pin "6") (pinfunction "SH1_6") (pintype "unspecified"))
      (node (ref "USB") (pin "7") (pinfunction "SH2_7") (pintype "unspecified"))
      (node (ref "USB") (pin "8") (pinfunction "SH3_8") (pintype "unspecified"))
      (node (ref "USB") (pin "9") (pinfunction "SH4_9") (pintype "unspecified"))
    )
    (net (code "7") (name "GNDD") (class "Default")
      (node (ref "CN1") (pin "3") (pinfunction "3_3") (pintype "unspecified"))
      (node (ref "CN1") (pin "4") (pinfunction "4_4") (pintype "unspecified"))
      (node (ref "CN1") (pin "5") (pinfunction "5_5") (pintype "unspecified"))
      (node (ref "CN6") (pin "3") (pinfunction "3_3") (pintype "unspecified"))
      (node (ref "CN6") (pin "4") (pinfunction "4_4") (pintype "unspecified"))
      (node (ref "CN6") (pin "5") (pinfunction "5_5") (pintype "unspecified"))
      (node (ref "L1") (pin "3") (pinfunction "VSS_3") (pintype "unspecified"))
      (node (ref "L10") (pin "3") (pinfunction "VSS_3") (pintype "unspecified"))
      (node (ref "L100") (pin "3") (pinfunction "VSS_3") (pintype "unspecified"))
      (node (ref "L101") (pin "3") (pinfunction "VSS_3") (pintype "unspecified"))
      (node (ref "L102") (pin "3") (pinfunction "VSS_3") (pintype "unspecified"))
      (node (ref "L103") (pin "3") (pinfunction "VSS_3") (pintype "unspecified"))
      (node (ref "L104") (pin "3") (pinfunction "VSS_3") (pintype "unspecified"))
      (node (ref "L105") (pin "3") (pinfunction "VSS_3") (pintype "unspecified"))
      (node (ref "L106") (pin "3") (pinfunction "VSS_3") (pintype "unspecified"))
      (node (ref "L107") (pin "3") (pinfunction "VSS_3") (pintype "unspecified"))
      (node (ref "L108") (pin "3") (pinfunction "VSS_3") (pintype "unspecified"))
      (node (ref "L109") (pin "3") (pinfunction "VSS_3") (pintype "unspecified"))
      (node (ref "L11") (pin "3") (pinfunction "VSS_3") (pintype "unspecified"))
      (node (ref "L110") (pin "3") (pinfunction "VSS_3") (pintype "unspecified"))
      (node (ref "L111") (pin "3") (pinfunction "VSS_3") (pintype "unspecified"))
      (node (ref "L112") (pin "3") (pinfunction "VSS_3") (pintype "unspecified"))
      (node (ref "L113") (pin "3") (pinfunction "VSS_3") (pintype "unspecified"))
      (node (ref "L114") (pin "3") (pinfunction "VSS_3") (pintype "unspecified"))
      (node (ref "L115") (pin "3") (pinfunction "VSS_3") (pintype "unspecified"))
      (node (ref "L116") (pin "3") (pinfunction "VSS_3") (pintype "unspecified"))
      (node (ref "L117") (pin "3") (pinfunction "VSS_3") (pintype "unspecified"))
      (node (ref "L118") (pin "3") (pinfunction "VSS_3") (pintype "unspecified"))
      (node (ref "L119") (pin "3") (pinfunction "VSS_3") (pintype "unspecified"))
      (node (ref "L12") (pin "3") (pinfunction "VSS_3") (pintype "unspecified"))
      (node (ref "L120") (pin "3") (pinfunction "VSS_3") (pintype "unspecified"))
      (node (ref "L121") (pin "3") (pinfunction "VSS_3") (pintype "unspecified"))
      (node (ref "L122") (pin "3") (pinfunction "VSS_3") (pintype "unspecified"))
      (node (ref "L123") (pin "3") (pinfunction "VSS_3") (pintype "unspecified"))
      (node (ref "L124") (pin "3") (pinfunction "VSS_3") (pintype "unspecified"))
      (node (ref "L125") (pin "3") (pinfunction "VSS_3") (pintype "unspecified"))
      (node (ref "L126") (pin "3") (pinfunction "VSS_3") (pintype "unspecified"))
      (node (ref "L127") (pin "3") (pinfunction "VSS_3") (pintype "unspecified"))
      (node (ref "L128") (pin "3") (pinfunction "VSS_3") (pintype "unspecified"))
      (node (ref "L13") (pin "3") (pinfunction "VSS_3") (pintype "unspecified"))
      (node (ref "L14") (pin "3") (pinfunction "VSS_3") (pintype "unspecified"))
      (node (ref "L15") (pin "3") (pinfunction "VSS_3") (pintype "unspecified"))
      (node (ref "L16") (pin "3") (pinfunction "VSS_3") (pintype "unspecified"))
      (node (ref "L17") (pin "3") (pinfunction "VSS_3") (pintype "unspecified"))
      (node (ref "L18") (pin "3") (pinfunction "VSS_3") (pintype "unspecified"))
      (node (ref "L19") (pin "3") (pinfunction "VSS_3") (pintype "unspecified"))
      (node (ref "L2") (pin "3") (pinfunction "VSS_3") (pintype "unspecified"))
      (node (ref "L20") (pin "3") (pinfunction "VSS_3") (pintype "unspecified"))
      (node (ref "L21") (pin "3") (pinfunction "VSS_3") (pintype "unspecified"))
      (node (ref "L22") (pin "3") (pinfunction "VSS_3") (pintype "unspecified"))
      (node (ref "L23") (pin "3") (pinfunction "VSS_3") (pintype "unspecified"))
      (node (ref "L24") (pin "3") (pinfunction "VSS_3") (pintype "unspecified"))
      (node (ref "L25") (pin "3") (pinfunction "VSS_3") (pintype "unspecified"))
      (node (ref "L26") (pin "3") (pinfunction "VSS_3") (pintype "unspecified"))
      (node (ref "L27") (pin "3") (pinfunction "VSS_3") (pintype "unspecified"))
      (node (ref "L28") (pin "3") (pinfunction "VSS_3") (pintype "unspecified"))
      (node (ref "L29") (pin "3") (pinfunction "VSS_3") (pintype "unspecified"))
      (node (ref "L3") (pin "3") (pinfunction "VSS_3") (pintype "unspecified"))
      (node (ref "L30") (pin "3") (pinfunction "VSS_3") (pintype "unspecified"))
      (node (ref "L31") (pin "3") (pinfunction "VSS_3") (pintype "unspecified"))
      (node (ref "L32") (pin "3") (pinfunction "VSS_3") (pintype "unspecified"))
      (node (ref "L33") (pin "3") (pinfunction "VSS_3") (pintype "unspecified"))
      (node (ref "L34") (pin "3") (pinfunction "VSS_3") (pintype "unspecified"))
      (node (ref "L35") (pin "3") (pinfunction "VSS_3") (pintype "unspecified"))
      (node (ref "L36") (pin "3") (pinfunction "VSS_3") (pintype "unspecified"))
      (node (ref "L37") (pin "3") (pinfunction "VSS_3") (pintype "unspecified"))
      (node (ref "L38") (pin "3") (pinfunction "VSS_3") (pintype "unspecified"))
      (node (ref "L39") (pin "3") (pinfunction "VSS_3") (pintype "unspecified"))
      (node (ref "L4") (pin "3") (pinfunction "VSS_3") (pintype "unspecified"))
      (node (ref "L40") (pin "3") (pinfunction "VSS_3") (pintype "unspecified"))
      (node (ref "L41") (pin "3") (pinfunction "VSS_3") (pintype "unspecified"))
      (node (ref "L42") (pin "3") (pinfunction "VSS_3") (pintype "unspecified"))
      (node (ref "L43") (pin "3") (pinfunction "VSS_3") (pintype "unspecified"))
      (node (ref "L44") (pin "3") (pinfunction "VSS_3") (pintype "unspecified"))
      (node (ref "L45") (pin "3") (pinfunction "VSS_3") (pintype "unspecified"))
      (node (ref "L46") (pin "3") (pinfunction "VSS_3") (pintype "unspecified"))
      (node (ref "L47") (pin "3") (pinfunction "VSS_3") (pintype "unspecified"))
      (node (ref "L48") (pin "3") (pinfunction "VSS_3") (pintype "unspecified"))
      (node (ref "L49") (pin "3") (pinfunction "VSS_3") (pintype "unspecified"))
      (node (ref "L5") (pin "3") (pinfunction "VSS_3") (pintype "unspecified"))
      (node (ref "L50") (pin "3") (pinfunction "VSS_3") (pintype "unspecified"))
      (node (ref "L51") (pin "3") (pinfunction "VSS_3") (pintype "unspecified"))
      (node (ref "L52") (pin "3") (pinfunction "VSS_3") (pintype "unspecified"))
      (node (ref "L53") (pin "3") (pinfunction "VSS_3") (pintype "unspecified"))
      (node (ref "L54") (pin "3") (pinfunction "VSS_3") (pintype "unspecified"))
      (node (ref "L55") (pin "3") (pinfunction "VSS_3") (pintype "unspecified"))
      (node (ref "L56") (pin "3") (pinfunction "VSS_3") (pintype "unspecified"))
      (node (ref "L57") (pin "3") (pinfunction "VSS_3") (pintype "unspecified"))
      (node (ref "L58") (pin "3") (pinfunction "VSS_3") (pintype "unspecified"))
      (node (ref "L59") (pin "3") (pinfunction "VSS_3") (pintype "unspecified"))
      (node (ref "L6") (pin "3") (pinfunction "VSS_3") (pintype "unspecified"))
      (node (ref "L60") (pin "3") (pinfunction "VSS_3") (pintype "unspecified"))
      (node (ref "L61") (pin "3") (pinfunction "VSS_3") (pintype "unspecified"))
      (node (ref "L62") (pin "3") (pinfunction "VSS_3") (pintype "unspecified"))
      (node (ref "L63") (pin "3") (pinfunction "VSS_3") (pintype "unspecified"))
      (node (ref "L64") (pin "3") (pinfunction "VSS_3") (pintype "unspecified"))
      (node (ref "L65") (pin "3") (pinfunction "VSS_3") (pintype "unspecified"))
      (node (ref "L66") (pin "3") (pinfunction "VSS_3") (pintype "unspecified"))
      (node (ref "L67") (pin "3") (pinfunction "VSS_3") (pintype "unspecified"))
      (node (ref "L68") (pin "3") (pinfunction "VSS_3") (pintype "unspecified"))
      (node (ref "L69") (pin "3") (pinfunction "VSS_3") (pintype "unspecified"))
      (node (ref "L7") (pin "3") (pinfunction "VSS_3") (pintype "unspecified"))
      (node (ref "L70") (pin "3") (pinfunction "VSS_3") (pintype "unspecified"))
      (node (ref "L71") (pin "3") (pinfunction "VSS_3") (pintype "unspecified"))
      (node (ref "L72") (pin "3") (pinfunction "VSS_3") (pintype "unspecified"))
      (node (ref "L73") (pin "3") (pinfunction "VSS_3") (pintype "unspecified"))
      (node (ref "L74") (pin "3") (pinfunction "VSS_3") (pintype "unspecified"))
      (node (ref "L75") (pin "3") (pinfunction "VSS_3") (pintype "unspecified"))
      (node (ref "L76") (pin "3") (pinfunction "VSS_3") (pintype "unspecified"))
      (node (ref "L77") (pin "3") (pinfunction "VSS_3") (pintype "unspecified"))
      (node (ref "L78") (pin "3") (pinfunction "VSS_3") (pintype "unspecified"))
      (node (ref "L79") (pin "3") (pinfunction "VSS_3") (pintype "unspecified"))
      (node (ref "L8") (pin "3") (pinfunction "VSS_3") (pintype "unspecified"))
      (node (ref "L80") (pin "3") (pinfunction "VSS_3") (pintype "unspecified"))
      (node (ref "L81") (pin "3") (pinfunction "VSS_3") (pintype "unspecified"))
      (node (ref "L82") (pin "3") (pinfunction "VSS_3") (pintype "unspecified"))
      (node (ref "L83") (pin "3") (pinfunction "VSS_3") (pintype "unspecified"))
      (node (ref "L84") (pin "3") (pinfunction "VSS_3") (pintype "unspecified"))
      (node (ref "L85") (pin "3") (pinfunction "VSS_3") (pintype "unspecified"))
      (node (ref "L86") (pin "3") (pinfunction "VSS_3") (pintype "unspecified"))
      (node (ref "L87") (pin "3") (pinfunction "VSS_3") (pintype "unspecified"))
      (node (ref "L88") (pin "3") (pinfunction "VSS_3") (pintype "unspecified"))
      (node (ref "L89") (pin "3") (pinfunction "VSS_3") (pintype "unspecified"))
      (node (ref "L9") (pin "3") (pinfunction "VSS_3") (pintype "unspecified"))
      (node (ref "L90") (pin "3") (pinfunction "VSS_3") (pintype "unspecified"))
      (node (ref "L91") (pin "3") (pinfunction "VSS_3") (pintype "unspecified"))
      (node (ref "L92") (pin "3") (pinfunction "VSS_3") (pintype "unspecified"))
      (node (ref "L93") (pin "3") (pinfunction "VSS_3") (pintype "unspecified"))
      (node (ref "L94") (pin "3") (pinfunction "VSS_3") (pintype "unspecified"))
      (node (ref "L95") (pin "3") (pinfunction "VSS_3") (pintype "unspecified"))
      (node (ref "L96") (pin "3") (pinfunction "VSS_3") (pintype "unspecified"))
      (node (ref "L97") (pin "3") (pinfunction "VSS_3") (pintype "unspecified"))
      (node (ref "L98") (pin "3") (pinfunction "VSS_3") (pintype "unspecified"))
      (node (ref "L99") (pin "3") (pinfunction "VSS_3") (pintype "unspecified"))
    )
    (net (code "8") (name "LED") (class "Default")
      (node (ref "H5") (pin "2") (pinfunction "2_2") (pintype "input"))
      (node (ref "LED3") (pin "2") (pinfunction "DI_2") (pintype "unspecified"))
    )
    (net (code "9") (name "LED3") (class "Default")
      (node (ref "LED3") (pin "4") (pinfunction "DO_4") (pintype "unspecified"))
      (node (ref "LED4") (pin "2") (pinfunction "DI_2") (pintype "unspecified"))
    )
    (net (code "10") (name "LED4") (class "Default")
      (node (ref "LED4") (pin "4") (pinfunction "DO_4") (pintype "unspecified"))
      (node (ref "LED5") (pin "2") (pinfunction "DI_2") (pintype "unspecified"))
    )
    (net (code "11") (name "LED5") (class "Default")
      (node (ref "LED5") (pin "4") (pinfunction "DO_4") (pintype "unspecified"))
      (node (ref "LED6") (pin "2") (pinfunction "DI_2") (pintype "unspecified"))
    )
    (net (code "12") (name "LED6") (class "Default")
      (node (ref "H5") (pin "3") (pinfunction "3_3") (pintype "input"))
      (node (ref "LED6") (pin "4") (pinfunction "DO_4") (pintype "unspecified"))
    )
    (net (code "13") (name "Net-(C6-Pad1)") (class "Default")
      (node (ref "C6") (pin "1") (pinfunction "1_1") (pintype "input"))
      (node (ref "MIC1") (pin "1") (pinfunction "1_1") (pintype "unspecified"))
      (node (ref "R1") (pin "1") (pinfunction "1_1") (pintype "unspecified"))
    )
    (net (code "14") (name "Net-(C9-Pad2)") (class "Default")
      (node (ref "C9") (pin "2") (pinfunction "2_2") (pintype "input"))
      (node (ref "R2") (pin "2") (pinfunction "2_2") (pintype "unspecified"))
    )
    (net (code "15") (name "Net-(D2-A)") (class "Default")
      (node (ref "D2") (pin "2") (pinfunction "A_2") (pintype "unspecified"))
      (node (ref "DC1") (pin "1") (pinfunction "1_1") (pintype "unspecified"))
    )
    (net (code "16") (name "Net-(H2-Pad2)") (class "Default")
      (node (ref "H2") (pin "2") (pinfunction "2_2") (pintype "input"))
      (node (ref "R14") (pin "2") (pinfunction "2_2") (pintype "unspecified"))
    )
    (net (code "17") (name "Net-(H3-Pad2)") (class "Default")
      (node (ref "H3") (pin "2") (pinfunction "2_2") (pintype "input"))
      (node (ref "R13") (pin "2") (pinfunction "2_2") (pintype "unspecified"))
    )
    (net (code "18") (name "Net-(L1-DOUT)") (class "Default")
      (node (ref "L1") (pin "2") (pinfunction "DOUT_2") (pintype "unspecified"))
      (node (ref "L2") (pin "4") (pinfunction "DIN_4") (pintype "unspecified"))
    )
    (net (code "19") (name "Net-(L2-DOUT)") (class "Default")
      (node (ref "L2") (pin "2") (pinfunction "DOUT_2") (pintype "unspecified"))
      (node (ref "L3") (pin "4") (pinfunction "DIN_4") (pintype "unspecified"))
    )
    (net (code "20") (name "Net-(L3-DOUT)") (class "Default")
      (node (ref "L3") (pin "2") (pinfunction "DOUT_2") (pintype "unspecified"))
      (node (ref "L4") (pin "4") (pinfunction "DIN_4") (pintype "unspecified"))
    )
    (net (code "21") (name "Net-(L4-DOUT)") (class "Default")
      (node (ref "L4") (pin "2") (pinfunction "DOUT_2") (pintype "unspecified"))
      (node (ref "L5") (pin "4") (pinfunction "DIN_4") (pintype "unspecified"))
    )
    (net (code "22") (name "Net-(L5-DOUT)") (class "Default")
      (node (ref "L5") (pin "2") (pinfunction "DOUT_2") (pintype "unspecified"))
      (node (ref "L6") (pin "4") (pinfunction "DIN_4") (pintype "unspecified"))
    )
    (net (code "23") (name "Net-(L6-DOUT)") (class "Default")
      (node (ref "L6") (pin "2") (pinfunction "DOUT_2") (pintype "unspecified"))
      (node (ref "L7") (pin "4") (pinfunction "DIN_4") (pintype "unspecified"))
    )
    (net (code "24") (name "Net-(L7-DOUT)") (class "Default")
      (node (ref "L7") (pin "2") (pinfunction "DOUT_2") (pintype "unspecified"))
      (node (ref "L8") (pin "4") (pinfunction "DIN_4") (pintype "unspecified"))
    )
    (net (code "25") (name "Net-(L10-DIN)") (class "Default")
      (node (ref "L10") (pin "4") (pinfunction "DIN_4") (pintype "unspecified"))
      (node (ref "L9") (pin "2") (pinfunction "DOUT_2") (pintype "unspecified"))
    )
    (net (code "26") (name "Net-(L10-DOUT)") (class "Default")
      (node (ref "L10") (pin "2") (pinfunction "DOUT_2") (pintype "unspecified"))
      (node (ref "L11") (pin "4") (pinfunction "DIN_4") (pintype "unspecified"))
    )
    (net (code "27") (name "Net-(L11-DOUT)") (class "Default")
      (node (ref "L11") (pin "2") (pinfunction "DOUT_2") (pintype "unspecified"))
      (node (ref "L12") (pin "4") (pinfunction "DIN_4") (pintype "unspecified"))
    )
    (net (code "28") (name "Net-(L12-DOUT)") (class "Default")
      (node (ref "L12") (pin "2") (pinfunction "DOUT_2") (pintype "unspecified"))
      (node (ref "L13") (pin "4") (pinfunction "DIN_4") (pintype "unspecified"))
    )
    (net (code "29") (name "Net-(L13-DOUT)") (class "Default")
      (node (ref "L13") (pin "2") (pinfunction "DOUT_2") (pintype "unspecified"))
      (node (ref "L14") (pin "4") (pinfunction "DIN_4") (pintype "unspecified"))
    )
    (net (code "30") (name "Net-(L14-DOUT)") (class "Default")
      (node (ref "L14") (pin "2") (pinfunction "DOUT_2") (pintype "unspecified"))
      (node (ref "L15") (pin "4") (pinfunction "DIN_4") (pintype "unspecified"))
    )
    (net (code "31") (name "Net-(L15-DOUT)") (class "Default")
      (node (ref "L15") (pin "2") (pinfunction "DOUT_2") (pintype "unspecified"))
      (node (ref "L16") (pin "4") (pinfunction "DIN_4") (pintype "unspecified"))
    )
    (net (code "32") (name "Net-(L17-DOUT)") (class "Default")
      (node (ref "L17") (pin "2") (pinfunction "DOUT_2") (pintype "unspecified"))
      (node (ref "L18") (pin "4") (pinfunction "DIN_4") (pintype "unspecified"))
    )
    (net (code "33") (name "Net-(L18-DOUT)") (class "Default")
      (node (ref "L18") (pin "2") (pinfunction "DOUT_2") (pintype "unspecified"))
      (node (ref "L19") (pin "4") (pinfunction "DIN_4") (pintype "unspecified"))
    )
    (net (code "34") (name "Net-(L19-DOUT)") (class "Default")
      (node (ref "L19") (pin "2") (pinfunction "DOUT_2") (pintype "unspecified"))
      (node (ref "L20") (pin "4") (pinfunction "DIN_4") (pintype "unspecified"))
    )
    (net (code "35") (name "Net-(L20-DOUT)") (class "Default")
      (node (ref "L20") (pin "2") (pinfunction "DOUT_2") (pintype "unspecified"))
      (node (ref "L21") (pin "4") (pinfunction "DIN_4") (pintype "unspecified"))
    )
    (net (code "36") (name "Net-(L21-DOUT)") (class "Default")
      (node (ref "L21") (pin "2") (pinfunction "DOUT_2") (pintype "unspecified"))
      (node (ref "L22") (pin "4") (pinfunction "DIN_4") (pintype "unspecified"))
    )
    (net (code "37") (name "Net-(L22-DOUT)") (class "Default")
      (node (ref "L22") (pin "2") (pinfunction "DOUT_2") (pintype "unspecified"))
      (node (ref "L23") (pin "4") (pinfunction "DIN_4") (pintype "unspecified"))
    )
    (net (code "38") (name "Net-(L23-DOUT)") (class "Default")
      (node (ref "L23") (pin "2") (pinfunction "DOUT_2") (pintype "unspecified"))
      (node (ref "L24") (pin "4") (pinfunction "DIN_4") (pintype "unspecified"))
    )
    (net (code "39") (name "Net-(L25-DOUT)") (class "Default")
      (node (ref "L25") (pin "2") (pinfunction "DOUT_2") (pintype "unspecified"))
      (node (ref "L26") (pin "4") (pinfunction "DIN_4") (pintype "unspecified"))
    )
    (net (code "40") (name "Net-(L26-DOUT)") (class "Default")
      (node (ref "L26") (pin "2") (pinfunction "DOUT_2") (pintype "unspecified"))
      (node (ref "L27") (pin "4") (pinfunction "DIN_4") (pintype "unspecified"))
    )
    (net (code "41") (name "Net-(L27-DOUT)") (class "Default")
      (node (ref "L27") (pin "2") (pinfunction "DOUT_2") (pintype "unspecified"))
      (node (ref "L28") (pin "4") (pinfunction "DIN_4") (pintype "unspecified"))
    )
    (net (code "42") (name "Net-(L28-DOUT)") (class "Default")
      (node (ref "L28") (pin "2") (pinfunction "DOUT_2") (pintype "unspecified"))
      (node (ref "L29") (pin "4") (pinfunction "DIN_4") (pintype "unspecified"))
    )
    (net (code "43") (name "Net-(L29-DOUT)") (class "Default")
      (node (ref "L29") (pin "2") (pinfunction "DOUT_2") (pintype "unspecified"))
      (node (ref "L30") (pin "4") (pinfunction "DIN_4") (pintype "unspecified"))
    )
    (net (code "44") (name "Net-(L30-DOUT)") (class "Default")
      (node (ref "L30") (pin "2") (pinfunction "DOUT_2") (pintype "unspecified"))
      (node (ref "L31") (pin "4") (pinfunction "DIN_4") (pintype "unspecified"))
    )
    (net (code "45") (name "Net-(L31-DOUT)") (class "Default")
      (node (ref "L31") (pin "2") (pinfunction "DOUT_2") (pintype "unspecified"))
      (node (ref "L32") (pin "4") (pinfunction "DIN_4") (pintype "unspecified"))
    )
    (net (code "46") (name "Net-(L33-DOUT)") (class "Default")
      (node (ref "L33") (pin "2") (pinfunction "DOUT_2") (pintype "unspecified"))
      (node (ref "L34") (pin "4") (pinfunction "DIN_4") (pintype "unspecified"))
    )
    (net (code "47") (name "Net-(L34-DOUT)") (class "Default")
      (node (ref "L34") (pin "2") (pinfunction "DOUT_2") (pintype "unspecified"))
      (node (ref "L35") (pin "4") (pinfunction "DIN_4") (pintype "unspecified"))
    )
    (net (code "48") (name "Net-(L35-DOUT)") (class "Default")
      (node (ref "L35") (pin "2") (pinfunction "DOUT_2") (pintype "unspecified"))
      (node (ref "L36") (pin "4") (pinfunction "DIN_4") (pintype "unspecified"))
    )
    (net (code "49") (name "Net-(L36-DOUT)") (class "Default")
      (node (ref "L36") (pin "2") (pinfunction "DOUT_2") (pintype "unspecified"))
      (node (ref "L37") (pin "4") (pinfunction "DIN_4") (pintype "unspecified"))
    )
    (net (code "50") (name "Net-(L37-DOUT)") (class "Default")
      (node (ref "L37") (pin "2") (pinfunction "DOUT_2") (pintype "unspecified"))
      (node (ref "L38") (pin "4") (pinfunction "DIN_4") (pintype "unspecified"))
    )
    (net (code "51") (name "Net-(L38-DOUT)") (class "Default")
      (node (ref "L38") (pin "2") (pinfunction "DOUT_2") (pintype "unspecified"))
      (node (ref "L39") (pin "4") (pinfunction "DIN_4") (pintype "unspecified"))
    )
    (net (code "52") (name "Net-(L39-DOUT)") (class "Default")
      (node (ref "L39") (pin "2") (pinfunction "DOUT_2") (pintype "unspecified"))
      (node (ref "L40") (pin "4") (pinfunction "DIN_4") (pintype "unspecified"))
    )
    (net (code "53") (name "Net-(L41-DOUT)") (class "Default")
      (node (ref "L41") (pin "2") (pinfunction "DOUT_2") (pintype "unspecified"))
      (node (ref "L42") (pin "4") (pinfunction "DIN_4") (pintype "unspecified"))
    )
    (net (code "54") (name "Net-(L42-DOUT)") (class "Default")
      (node (ref "L42") (pin "2") (pinfunction "DOUT_2") (pintype "unspecified"))
      (node (ref "L43") (pin "4") (pinfunction "DIN_4") (pintype "unspecified"))
    )
    (net (code "55") (name "Net-(L43-DOUT)") (class "Default")
      (node (ref "L43") (pin "2") (pinfunction "DOUT_2") (pintype "unspecified"))
      (node (ref "L44") (pin "4") (pinfunction "DIN_4") (pintype "unspecified"))
    )
    (net (code "56") (name "Net-(L44-DOUT)") (class "Default")
      (node (ref "L44") (pin "2") (pinfunction "DOUT_2") (pintype "unspecified"))
      (node (ref "L45") (pin "4") (pinfunction "DIN_4") (pintype "unspecified"))
    )
    (net (code "57") (name "Net-(L45-DOUT)") (class "Default")
      (node (ref "L45") (pin "2") (pinfunction "DOUT_2") (pintype "unspecified"))
      (node (ref "L46") (pin "4") (pinfunction "DIN_4") (pintype "unspecified"))
    )
    (net (code "58") (name "Net-(L46-DOUT)") (class "Default")
      (node (ref "L46") (pin "2") (pinfunction "DOUT_2") (pintype "unspecified"))
      (node (ref "L47") (pin "4") (pinfunction "DIN_4") (pintype "unspecified"))
    )
    (net (code "59") (name "Net-(L47-DOUT)") (class "Default")
      (node (ref "L47") (pin "2") (pinfunction "DOUT_2") (pintype "unspecified"))
      (node (ref "L48") (pin "4") (pinfunction "DIN_4") (pintype "unspecified"))
    )
    (net (code "60") (name "Net-(L49-DOUT)") (class "Default")
      (node (ref "L49") (pin "2") (pinfunction "DOUT_2") (pintype "unspecified"))
      (node (ref "L50") (pin "4") (pinfunction "DIN_4") (pintype "unspecified"))
    )
    (net (code "61") (name "Net-(L50-DOUT)") (class "Default")
      (node (ref "L50") (pin "2") (pinfunction "DOUT_2") (pintype "unspecified"))
      (node (ref "L51") (pin "4") (pinfunction "DIN_4") (pintype "unspecified"))
    )
    (net (code "62") (name "Net-(L51-DOUT)") (class "Default")
      (node (ref "L51") (pin "2") (pinfunction "DOUT_2") (pintype "unspecified"))
      (node (ref "L52") (pin "4") (pinfunction "DIN_4") (pintype "unspecified"))
    )
    (net (code "63") (name "Net-(L52-DOUT)") (class "Default")
      (node (ref "L52") (pin "2") (pinfunction "DOUT_2") (pintype "unspecified"))
      (node (ref "L53") (pin "4") (pinfunction "DIN_4") (pintype "unspecified"))
    )
    (net (code "64") (name "Net-(L53-DOUT)") (class "Default")
      (node (ref "L53") (pin "2") (pinfunction "DOUT_2") (pintype "unspecified"))
      (node (ref "L54") (pin "4") (pinfunction "DIN_4") (pintype "unspecified"))
    )
    (net (code "65") (name "Net-(L54-DOUT)") (class "Default")
      (node (ref "L54") (pin "2") (pinfunction "DOUT_2") (pintype "unspecified"))
      (node (ref "L55") (pin "4") (pinfunction "DIN_4") (pintype "unspecified"))
    )
    (net (code "66") (name "Net-(L55-DOUT)") (class "Default")
      (node (ref "L55") (pin "2") (pinfunction "DOUT_2") (pintype "unspecified"))
      (node (ref "L56") (pin "4") (pinfunction "DIN_4") (pintype "unspecified"))
    )
    (net (code "67") (name "Net-(L57-DOUT)") (class "Default")
      (node (ref "L57") (pin "2") (pinfunction "DOUT_2") (pintype "unspecified"))
      (node (ref "L58") (pin "4") (pinfunction "DIN_4") (pintype "unspecified"))
    )
    (net (code "68") (name "Net-(L58-DOUT)") (class "Default")
      (node (ref "L58") (pin "2") (pinfunction "DOUT_2") (pintype "unspecified"))
      (node (ref "L59") (pin "4") (pinfunction "DIN_4") (pintype "unspecified"))
    )
    (net (code "69") (name "Net-(L59-DOUT)") (class "Default")
      (node (ref "L59") (pin "2") (pinfunction "DOUT_2") (pintype "unspecified"))
      (node (ref "L60") (pin "4") (pinfunction "DIN_4") (pintype "unspecified"))
    )
    (net (code "70") (name "Net-(L60-DOUT)") (class "Default")
      (node (ref "L60") (pin "2") (pinfunction "DOUT_2") (pintype "unspecified"))
      (node (ref "L61") (pin "4") (pinfunction "DIN_4") (pintype "unspecified"))
    )
    (net (code "71") (name "Net-(L61-DOUT)") (class "Default")
      (node (ref "L61") (pin "2") (pinfunction "DOUT_2") (pintype "unspecified"))
      (node (ref "L62") (pin "4") (pinfunction "DIN_4") (pintype "unspecified"))
    )
    (net (code "72") (name "Net-(L62-DOUT)") (class "Default")
      (node (ref "L62") (pin "2") (pinfunction "DOUT_2") (pintype "unspecified"))
      (node (ref "L63") (pin "4") (pinfunction "DIN_4") (pintype "unspecified"))
    )
    (net (code "73") (name "Net-(L63-DOUT)") (class "Default")
      (node (ref "L63") (pin "2") (pinfunction "DOUT_2") (pintype "unspecified"))
      (node (ref "L64") (pin "4") (pinfunction "DIN_4") (pintype "unspecified"))
    )
    (net (code "74") (name "Net-(L65-DOUT)") (class "Default")
      (node (ref "L65") (pin "2") (pinfunction "DOUT_2") (pintype "unspecified"))
      (node (ref "L66") (pin "4") (pinfunction "DIN_4") (pintype "unspecified"))
    )
    (net (code "75") (name "Net-(L66-DOUT)") (class "Default")
      (node (ref "L66") (pin "2") (pinfunction "DOUT_2") (pintype "unspecified"))
      (node (ref "L67") (pin "4") (pinfunction "DIN_4") (pintype "unspecified"))
    )
    (net (code "76") (name "Net-(L67-DOUT)") (class "Default")
      (node (ref "L67") (pin "2") (pinfunction "DOUT_2") (pintype "unspecified"))
      (node (ref "L68") (pin "4") (pinfunction "DIN_4") (pintype "unspecified"))
    )
    (net (code "77") (name "Net-(L68-DOUT)") (class "Default")
      (node (ref "L68") (pin "2") (pinfunction "DOUT_2") (pintype "unspecified"))
      (node (ref "L69") (pin "4") (pinfunction "DIN_4") (pintype "unspecified"))
    )
    (net (code "78") (name "Net-(L69-DOUT)") (class "Default")
      (node (ref "L69") (pin "2") (pinfunction "DOUT_2") (pintype "unspecified"))
      (node (ref "L70") (pin "4") (pinfunction "DIN_4") (pintype "unspecified"))
    )
    (net (code "79") (name "Net-(L70-DOUT)") (class "Default")
      (node (ref "L70") (pin "2") (pinfunction "DOUT_2") (pintype "unspecified"))
      (node (ref "L71") (pin "4") (pinfunction "DIN_4") (pintype "unspecified"))
    )
    (net (code "80") (name "Net-(L71-DOUT)") (class "Default")
      (node (ref "L71") (pin "2") (pinfunction "DOUT_2") (pintype "unspecified"))
      (node (ref "L72") (pin "4") (pinfunction "DIN_4") (pintype "unspecified"))
    )
    (net (code "81") (name "Net-(L73-DOUT)") (class "Default")
      (node (ref "L73") (pin "2") (pinfunction "DOUT_2") (pintype "unspecified"))
      (node (ref "L74") (pin "4") (pinfunction "DIN_4") (pintype "unspecified"))
    )
    (net (code "82") (name "Net-(L74-DOUT)") (class "Default")
      (node (ref "L74") (pin "2") (pinfunction "DOUT_2") (pintype "unspecified"))
      (node (ref "L75") (pin "4") (pinfunction "DIN_4") (pintype "unspecified"))
    )
    (net (code "83") (name "Net-(L75-DOUT)") (class "Default")
      (node (ref "L75") (pin "2") (pinfunction "DOUT_2") (pintype "unspecified"))
      (node (ref "L76") (pin "4") (pinfunction "DIN_4") (pintype "unspecified"))
    )
    (net (code "84") (name "Net-(L76-DOUT)") (class "Default")
      (node (ref "L76") (pin "2") (pinfunction "DOUT_2") (pintype "unspecified"))
      (node (ref "L77") (pin "4") (pinfunction "DIN_4") (pintype "unspecified"))
    )
    (net (code "85") (name "Net-(L77-DOUT)") (class "Default")
      (node (ref "L77") (pin "2") (pinfunction "DOUT_2") (pintype "unspecified"))
      (node (ref "L78") (pin "4") (pinfunction "DIN_4") (pintype "unspecified"))
    )
    (net (code "86") (name "Net-(L78-DOUT)") (class "Default")
      (node (ref "L78") (pin "2") (pinfunction "DOUT_2") (pintype "unspecified"))
      (node (ref "L79") (pin "4") (pinfunction "DIN_4") (pintype "unspecified"))
    )
    (net (code "87") (name "Net-(L79-DOUT)") (class "Default")
      (node (ref "L79") (pin "2") (pinfunction "DOUT_2") (pintype "unspecified"))
      (node (ref "L80") (pin "4") (pinfunction "DIN_4") (pintype "unspecified"))
    )
    (net (code "88") (name "Net-(L81-DOUT)") (class "Default")
      (node (ref "L81") (pin "2") (pinfunction "DOUT_2") (pintype "unspecified"))
      (node (ref "L82") (pin "4") (pinfunction "DIN_4") (pintype "unspecified"))
    )
    (net (code "89") (name "Net-(L82-DOUT)") (class "Default")
      (node (ref "L82") (pin "2") (pinfunction "DOUT_2") (pintype "unspecified"))
      (node (ref "L83") (pin "4") (pinfunction "DIN_4") (pintype "unspecified"))
    )
    (net (code "90") (name "Net-(L83-DOUT)") (class "Default")
      (node (ref "L83") (pin "2") (pinfunction "DOUT_2") (pintype "unspecified"))
      (node (ref "L84") (pin "4") (pinfunction "DIN_4") (pintype "unspecified"))
    )
    (net (code "91") (name "Net-(L84-DOUT)") (class "Default")
      (node (ref "L84") (pin "2") (pinfunction "DOUT_2") (pintype "unspecified"))
      (node (ref "L85") (pin "4") (pinfunction "DIN_4") (pintype "unspecified"))
    )
    (net (code "92") (name "Net-(L85-DOUT)") (class "Default")
      (node (ref "L85") (pin "2") (pinfunction "DOUT_2") (pintype "unspecified"))
      (node (ref "L86") (pin "4") (pinfunction "DIN_4") (pintype "unspecified"))
    )
    (net (code "93") (name "Net-(L86-DOUT)") (class "Default")
      (node (ref "L86") (pin "2") (pinfunction "DOUT_2") (pintype "unspecified"))
      (node (ref "L87") (pin "4") (pinfunction "DIN_4") (pintype "unspecified"))
    )
    (net (code "94") (name "Net-(L87-DOUT)") (class "Default")
      (node (ref "L87") (pin "2") (pinfunction "DOUT_2") (pintype "unspecified"))
      (node (ref "L88") (pin "4") (pinfunction "DIN_4") (pintype "unspecified"))
    )
    (net (code "95") (name "Net-(L89-DOUT)") (class "Default")
      (node (ref "L89") (pin "2") (pinfunction "DOUT_2") (pintype "unspecified"))
      (node (ref "L90") (pin "4") (pinfunction "DIN_4") (pintype "unspecified"))
    )
    (net (code "96") (name "Net-(L90-DOUT)") (class "Default")
      (node (ref "L90") (pin "2") (pinfunction "DOUT_2") (pintype "unspecified"))
      (node (ref "L91") (pin "4") (pinfunction "DIN_4") (pintype "unspecified"))
    )
    (net (code "97") (name "Net-(L91-DOUT)") (class "Default")
      (node (ref "L91") (pin "2") (pinfunction "DOUT_2") (pintype "unspecified"))
      (node (ref "L92") (pin "4") (pinfunction "DIN_4") (pintype "unspecified"))
    )
    (net (code "98") (name "Net-(L92-DOUT)") (class "Default")
      (node (ref "L92") (pin "2") (pinfunction "DOUT_2") (pintype "unspecified"))
      (node (ref "L93") (pin "4") (pinfunction "DIN_4") (pintype "unspecified"))
    )
    (net (code "99") (name "Net-(L93-DOUT)") (class "Default")
      (node (ref "L93") (pin "2") (pinfunction "DOUT_2") (pintype "unspecified"))
      (node (ref "L94") (pin "4") (pinfunction "DIN_4") (pintype "unspecified"))
    )
    (net (code "100") (name "Net-(L94-DOUT)") (class "Default")
      (node (ref "L94") (pin "2") (pinfunction "DOUT_2") (pintype "unspecified"))
      (node (ref "L95") (pin "4") (pinfunction "DIN_4") (pintype "unspecified"))
    )
    (net (code "101") (name "Net-(L95-DOUT)") (class "Default")
      (node (ref "L95") (pin "2") (pinfunction "DOUT_2") (pintype "unspecified"))
      (node (ref "L96") (pin "4") (pinfunction "DIN_4") (pintype "unspecified"))
    )
    (net (code "102") (name "Net-(L97-DOUT)") (class "Default")
      (node (ref "L97") (pin "2") (pinfunction "DOUT_2") (pintype "unspecified"))
      (node (ref "L98") (pin "4") (pinfunction "DIN_4") (pintype "unspecified"))
    )
    (net (code "103") (name "Net-(L98-DOUT)") (class "Default")
      (node (ref "L98") (pin "2") (pinfunction "DOUT_2") (pintype "unspecified"))
      (node (ref "L99") (pin "4") (pinfunction "DIN_4") (pintype "unspecified"))
    )
    (net (code "104") (name "Net-(L100-DIN)") (class "Default")
      (node (ref "L100") (pin "4") (pinfunction "DIN_4") (pintype "unspecified"))
      (node (ref "L99") (pin "2") (pinfunction "DOUT_2") (pintype "unspecified"))
    )
    (net (code "105") (name "Net-(L100-DOUT)") (class "Default")
      (node (ref "L100") (pin "2") (pinfunction "DOUT_2") (pintype "unspecified"))
      (node (ref "L101") (pin "4") (pinfunction "DIN_4") (pintype "unspecified"))
    )
    (net (code "106") (name "Net-(L101-DOUT)") (class "Default")
      (node (ref "L101") (pin "2") (pinfunction "DOUT_2") (pintype "unspecified"))
      (node (ref "L102") (pin "4") (pinfunction "DIN_4") (pintype "unspecified"))
    )
    (net (code "107") (name "Net-(L102-DOUT)") (class "Default")
      (node (ref "L102") (pin "2") (pinfunction "DOUT_2") (pintype "unspecified"))
      (node (ref "L103") (pin "4") (pinfunction "DIN_4") (pintype "unspecified"))
    )
    (net (code "108") (name "Net-(L103-DOUT)") (class "Default")
      (node (ref "L103") (pin "2") (pinfunction "DOUT_2") (pintype "unspecified"))
      (node (ref "L104") (pin "4") (pinfunction "DIN_4") (pintype "unspecified"))
    )
    (net (code "109") (name "Net-(L105-DOUT)") (class "Default")
      (node (ref "L105") (pin "2") (pinfunction "DOUT_2") (pintype "unspecified"))
      (node (ref "L106") (pin "4") (pinfunction "DIN_4") (pintype "unspecified"))
    )
    (net (code "110") (name "Net-(L106-DOUT)") (class "Default")
      (node (ref "L106") (pin "2") (pinfunction "DOUT_2") (pintype "unspecified"))
      (node (ref "L107") (pin "4") (pinfunction "DIN_4") (pintype "unspecified"))
    )
    (net (code "111") (name "Net-(L107-DOUT)") (class "Default")
      (node (ref "L107") (pin "2") (pinfunction "DOUT_2") (pintype "unspecified"))
      (node (ref "L108") (pin "4") (pinfunction "DIN_4") (pintype "unspecified"))
    )
    (net (code "112") (name "Net-(L108-DOUT)") (class "Default")
      (node (ref "L108") (pin "2") (pinfunction "DOUT_2") (pintype "unspecified"))
      (node (ref "L109") (pin "4") (pinfunction "DIN_4") (pintype "unspecified"))
    )
    (net (code "113") (name "Net-(L109-DOUT)") (class "Default")
      (node (ref "L109") (pin "2") (pinfunction "DOUT_2") (pintype "unspecified"))
      (node (ref "L110") (pin "4") (pinfunction "DIN_4") (pintype "unspecified"))
    )
    (net (code "114") (name "Net-(L110-DOUT)") (class "Default")
      (node (ref "L110") (pin "2") (pinfunction "DOUT_2") (pintype "unspecified"))
      (node (ref "L111") (pin "4") (pinfunction "DIN_4") (pintype "unspecified"))
    )
    (net (code "115") (name "Net-(L111-DOUT)") (class "Default")
      (node (ref "L111") (pin "2") (pinfunction "DOUT_2") (pintype "unspecified"))
      (node (ref "L112") (pin "4") (pinfunction "DIN_4") (pintype "unspecified"))
    )
    (net (code "116") (name "Net-(L113-DOUT)") (class "Default")
      (node (ref "L113") (pin "2") (pinfunction "DOUT_2") (pintype "unspecified"))
      (node (ref "L114") (pin "4") (pinfunction "DIN_4") (pintype "unspecified"))
    )
    (net (code "117") (name "Net-(L114-DOUT)") (class "Default")
      (node (ref "L114") (pin "2") (pinfunction "DOUT_2") (pintype "unspecified"))
      (node (ref "L115") (pin "4") (pinfunction "DIN_4") (pintype "unspecified"))
    )
    (net (code "118") (name "Net-(L115-DOUT)") (class "Default")
      (node (ref "L115") (pin "2") (pinfunction "DOUT_2") (pintype "unspecified"))
      (node (ref "L116") (pin "4") (pinfunction "DIN_4") (pintype "unspecified"))
    )
    (net (code "119") (name "Net-(L116-DOUT)") (class "Default")
      (node (ref "L116") (pin "2") (pinfunction "DOUT_2") (pintype "unspecified"))
      (node (ref "L117") (pin "4") (pinfunction "DIN_4") (pintype "unspecified"))
    )
    (net (code "120") (name "Net-(L117-DOUT)") (class "Default")
      (node (ref "L117") (pin "2") (pinfunction "DOUT_2") (pintype "unspecified"))
      (node (ref "L118") (pin "4") (pinfunction "DIN_4") (pintype "unspecified"))
    )
    (net (code "121") (name "Net-(L118-DOUT)") (class "Default")
      (node (ref "L118") (pin "2") (pinfunction "DOUT_2") (pintype "unspecified"))
      (node (ref "L119") (pin "4") (pinfunction "DIN_4") (pintype "unspecified"))
    )
    (net (code "122") (name "Net-(L119-DOUT)") (class "Default")
      (node (ref "L119") (pin "2") (pinfunction "DOUT_2") (pintype "unspecified"))
      (node (ref "L120") (pin "4") (pinfunction "DIN_4") (pintype "unspecified"))
    )
    (net (code "123") (name "Net-(L121-DOUT)") (class "Default")
      (node (ref "L121") (pin "2") (pinfunction "DOUT_2") (pintype "unspecified"))
      (node (ref "L122") (pin "4") (pinfunction "DIN_4") (pintype "unspecified"))
    )
    (net (code "124") (name "Net-(L122-DOUT)") (class "Default")
      (node (ref "L122") (pin "2") (pinfunction "DOUT_2") (pintype "unspecified"))
      (node (ref "L123") (pin "4") (pinfunction "DIN_4") (pintype "unspecified"))
    )
    (net (code "125") (name "Net-(L123-DOUT)") (class "Default")
      (node (ref "L123") (pin "2") (pinfunction "DOUT_2") (pintype "unspecified"))
      (node (ref "L124") (pin "4") (pinfunction "DIN_4") (pintype "unspecified"))
    )
    (net (code "126") (name "Net-(L124-DOUT)") (class "Default")
      (node (ref "L124") (pin "2") (pinfunction "DOUT_2") (pintype "unspecified"))
      (node (ref "L125") (pin "4") (pinfunction "DIN_4") (pintype "unspecified"))
    )
    (net (code "127") (name "Net-(L125-DOUT)") (class "Default")
      (node (ref "L125") (pin "2") (pinfunction "DOUT_2") (pintype "unspecified"))
      (node (ref "L126") (pin "4") (pinfunction "DIN_4") (pintype "unspecified"))
    )
    (net (code "128") (name "Net-(L126-DOUT)") (class "Default")
      (node (ref "L126") (pin "2") (pinfunction "DOUT_2") (pintype "unspecified"))
      (node (ref "L127") (pin "4") (pinfunction "DIN_4") (pintype "unspecified"))
    )
    (net (code "129") (name "Net-(L127-DOUT)") (class "Default")
      (node (ref "L127") (pin "2") (pinfunction "DOUT_2") (pintype "unspecified"))
      (node (ref "L128") (pin "4") (pinfunction "DIN_4") (pintype "unspecified"))
    )
    (net (code "130") (name "Net-(LED1-A)") (class "Default")
      (node (ref "LED1") (pin "1") (pinfunction "A_1") (pintype "input"))
      (node (ref "R15") (pin "1") (pinfunction "1_1") (pintype "input"))
    )
    (net (code "131") (name "Net-(LED2-A)") (class "Default")
      (node (ref "LED2") (pin "1") (pinfunction "A_1") (pintype "input"))
      (node (ref "R8") (pin "1") (pinfunction "1_1") (pintype "input"))
    )
    (net (code "132") (name "Net-(LED7-A)") (class "Default")
      (node (ref "LED7") (pin "1") (pinfunction "A_1") (pintype "unspecified"))
      (node (ref "R16") (pin "2") (pinfunction "2_2") (pintype "input"))
    )
    (net (code "133") (name "Net-(Q1-B)") (class "Default")
      (node (ref "Q1") (pin "1") (pinfunction "B_1") (pintype "input"))
      (node (ref "R9") (pin "1") (pinfunction "1_1") (pintype "unspecified"))
    )
    (net (code "134") (name "Net-(R4-Pad1)") (class "Default")
      (node (ref "R4") (pin "1") (pinfunction "1_1") (pintype "unspecified"))
      (node (ref "R5") (pin "2") (pinfunction "2_2") (pintype "unspecified"))
    )
    (net (code "135") (name "Net-(U3-+IN)") (class "Default")
      (node (ref "C6") (pin "2") (pinfunction "2_2") (pintype "input"))
      (node (ref "U3") (pin "1") (pinfunction "+IN_1") (pintype "unspecified"))
    )
    (net (code "136") (name "Net-(U3--IN)") (class "Default")
      (node (ref "R2") (pin "1") (pinfunction "1_1") (pintype "unspecified"))
      (node (ref "R5") (pin "1") (pinfunction "1_1") (pintype "unspecified"))
      (node (ref "U3") (pin "3") (pinfunction "-IN_3") (pintype "unspecified"))
    )
    (net (code "137") (name "Net-(U3-OUT)") (class "Default")
      (node (ref "C8") (pin "1") (pinfunction "1_1") (pintype "input"))
      (node (ref "R4") (pin "2") (pinfunction "2_2") (pintype "unspecified"))
      (node (ref "U3") (pin "4") (pinfunction "OUT_4") (pintype "unspecified"))
    )
    (net (code "138") (name "Net-(U4-OUTPUT)") (class "Default")
      (node (ref "D3") (pin "1") (pinfunction "1_1") (pintype "unspecified"))
      (node (ref "LL1") (pin "1") (pinfunction "1_1") (pintype "unspecified"))
      (node (ref "U4") (pin "2") (pinfunction "OUTPUT_2") (pintype "unspecified"))
    )
    (net (code "139") (name "OUT1") (class "Default")
      (node (ref "L8") (pin "2") (pinfunction "DOUT_2") (pintype "unspecified"))
      (node (ref "L9") (pin "4") (pinfunction "DIN_4") (pintype "unspecified"))
    )
    (net (code "140") (name "OUT2") (class "Default")
      (node (ref "L16") (pin "2") (pinfunction "DOUT_2") (pintype "unspecified"))
      (node (ref "L17") (pin "4") (pinfunction "DIN_4") (pintype "unspecified"))
    )
    (net (code "141") (name "OUT3") (class "Default")
      (node (ref "L24") (pin "2") (pinfunction "DOUT_2") (pintype "unspecified"))
      (node (ref "L25") (pin "4") (pinfunction "DIN_4") (pintype "unspecified"))
    )
    (net (code "142") (name "OUT4") (class "Default")
      (node (ref "L32") (pin "2") (pinfunction "DOUT_2") (pintype "unspecified"))
      (node (ref "L33") (pin "4") (pinfunction "DIN_4") (pintype "unspecified"))
    )
    (net (code "143") (name "OUT5") (class "Default")
      (node (ref "L40") (pin "2") (pinfunction "DOUT_2") (pintype "unspecified"))
      (node (ref "L41") (pin "4") (pinfunction "DIN_4") (pintype "unspecified"))
    )
    (net (code "144") (name "OUT6") (class "Default")
      (node (ref "L48") (pin "2") (pinfunction "DOUT_2") (pintype "unspecified"))
      (node (ref "L49") (pin "4") (pinfunction "DIN_4") (pintype "unspecified"))
    )
    (net (code "145") (name "OUT7") (class "Default")
      (node (ref "L56") (pin "2") (pinfunction "DOUT_2") (pintype "unspecified"))
      (node (ref "L57") (pin "4") (pinfunction "DIN_4") (pintype "unspecified"))
    )
    (net (code "146") (name "OUT8") (class "Default")
      (node (ref "L64") (pin "2") (pinfunction "DOUT_2") (pintype "unspecified"))
      (node (ref "L65") (pin "4") (pinfunction "DIN_4") (pintype "unspecified"))
    )
    (net (code "147") (name "OUT9") (class "Default")
      (node (ref "L72") (pin "2") (pinfunction "DOUT_2") (pintype "unspecified"))
      (node (ref "L73") (pin "4") (pinfunction "DIN_4") (pintype "unspecified"))
    )
    (net (code "148") (name "OUT10") (class "Default")
      (node (ref "L80") (pin "2") (pinfunction "DOUT_2") (pintype "unspecified"))
      (node (ref "L81") (pin "4") (pinfunction "DIN_4") (pintype "unspecified"))
    )
    (net (code "149") (name "OUT11") (class "Default")
      (node (ref "L88") (pin "2") (pinfunction "DOUT_2") (pintype "unspecified"))
      (node (ref "L89") (pin "4") (pinfunction "DIN_4") (pintype "unspecified"))
    )
    (net (code "150") (name "OUT12") (class "Default")
      (node (ref "L96") (pin "2") (pinfunction "DOUT_2") (pintype "unspecified"))
      (node (ref "L97") (pin "4") (pinfunction "DIN_4") (pintype "unspecified"))
    )
    (net (code "151") (name "OUT13") (class "Default")
      (node (ref "L104") (pin "2") (pinfunction "DOUT_2") (pintype "unspecified"))
      (node (ref "L105") (pin "4") (pinfunction "DIN_4") (pintype "unspecified"))
    )
    (net (code "152") (name "OUT14") (class "Default")
      (node (ref "L112") (pin "2") (pinfunction "DOUT_2") (pintype "unspecified"))
      (node (ref "L113") (pin "4") (pinfunction "DIN_4") (pintype "unspecified"))
    )
    (net (code "153") (name "OUT15") (class "Default")
      (node (ref "L120") (pin "2") (pinfunction "DOUT_2") (pintype "unspecified"))
      (node (ref "L121") (pin "4") (pinfunction "DIN_4") (pintype "unspecified"))
    )
    (net (code "154") (name "OUT_DATA") (class "Default")
      (node (ref "Q1") (pin "2") (pinfunction "E_2") (pintype "input"))
      (node (ref "R10") (pin "1") (pinfunction "1_1") (pintype "unspecified"))
      (node (ref "R12") (pin "1") (pinfunction "1_1") (pintype "input"))
    )
    (net (code "155") (name "OUT_RGB") (class "Default")
      (node (ref "H4") (pin "3") (pinfunction "3_3") (pintype "unspecified"))
      (node (ref "H5") (pin "1") (pinfunction "1_1") (pintype "input"))
      (node (ref "R13") (pin "1") (pinfunction "1_1") (pintype "unspecified"))
      (node (ref "R14") (pin "1") (pinfunction "1_1") (pintype "unspecified"))
    )
    (net (code "156") (name "OUT_RGB_ARD") (class "Default")
      (node (ref "H4") (pin "1") (pinfunction "1_1") (pintype "unspecified"))
      (node (ref "H4") (pin "2") (pinfunction "2_2") (pintype "unspecified"))
    )
    (net (code "157") (name "OUT_RGB_CBU") (class "Default")
      (node (ref "H4") (pin "4") (pinfunction "4_4") (pintype "unspecified"))
      (node (ref "Q1") (pin "3") (pinfunction "C_3") (pintype "input"))
      (node (ref "R11") (pin "1") (pinfunction "1_1") (pintype "unspecified"))
      (node (ref "R12") (pin "2") (pinfunction "2_2") (pintype "input"))
    )
    (net (code "158") (name "P6") (class "Default")
      (node (ref "H8") (pin "3") (pinfunction "3_3") (pintype "unspecified"))
      (node (ref "U1") (pin "10") (pinfunction "P6_10") (pintype "unspecified"))
    )
    (net (code "159") (name "P7") (class "Default")
      (node (ref "H8") (pin "2") (pinfunction "2_2") (pintype "unspecified"))
      (node (ref "U1") (pin "9") (pinfunction "P7_9") (pintype "unspecified"))
    )
    (net (code "160") (name "P8") (class "Default")
      (node (ref "H8") (pin "1") (pinfunction "1_1") (pintype "unspecified"))
      (node (ref "U1") (pin "8") (pinfunction "P8_8") (pintype "unspecified"))
    )
    (net (code "161") (name "P9") (class "Default")
      (node (ref "H7") (pin "3") (pinfunction "3_3") (pintype "unspecified"))
      (node (ref "U1") (pin "19") (pinfunction "P9_19") (pintype "unspecified"))
    )
    (net (code "162") (name "P14") (class "Default")
      (node (ref "H6") (pin "1") (pinfunction "1_1") (pintype "unspecified"))
      (node (ref "U1") (pin "1") (pinfunction "P14_1") (pintype "unspecified"))
    )
    (net (code "163") (name "P15") (class "Default")
      (node (ref "H7") (pin "1") (pinfunction "1_1") (pintype "unspecified"))
      (node (ref "U1") (pin "21") (pinfunction "P15_21") (pintype "unspecified"))
    )
    (net (code "164") (name "P16") (class "Default")
      (node (ref "H6") (pin "2") (pinfunction "2_2") (pintype "unspecified"))
      (node (ref "U1") (pin "2") (pinfunction "P16_2") (pintype "unspecified"))
    )
    (net (code "165") (name "P17") (class "Default")
      (node (ref "H7") (pin "2") (pinfunction "2_2") (pintype "unspecified"))
      (node (ref "U1") (pin "20") (pinfunction "P17_20") (pintype "unspecified"))
    )
    (net (code "166") (name "P20") (class "Default")
      (node (ref "C11") (pin "2") (pinfunction "2_2") (pintype "input"))
      (node (ref "H6") (pin "3") (pinfunction "3_3") (pintype "unspecified"))
      (node (ref "R6") (pin "1") (pinfunction "1_1") (pintype "unspecified"))
      (node (ref "SW1") (pin "2") (pinfunction "2_2") (pintype "input"))
      (node (ref "U1") (pin "3") (pinfunction "P20_3") (pintype "unspecified"))
    )
    (net (code "167") (name "P22") (class "Default")
      (node (ref "C12") (pin "2") (pinfunction "2_2") (pintype "input"))
      (node (ref "H6") (pin "4") (pinfunction "4_4") (pintype "unspecified"))
      (node (ref "R7") (pin "1") (pinfunction "1_1") (pintype "unspecified"))
      (node (ref "SW3") (pin "2") (pinfunction "2_2") (pintype "input"))
      (node (ref "U1") (pin "4") (pinfunction "P22_4") (pintype "unspecified"))
    )
    (net (code "168") (name "P24") (class "Default")
      (node (ref "H8") (pin "5") (pinfunction "5_5") (pintype "unspecified"))
      (node (ref "R15") (pin "2") (pinfunction "2_2") (pintype "input"))
      (node (ref "U1") (pin "12") (pinfunction "P24_12") (pintype "unspecified"))
    )
    (net (code "169") (name "P26") (class "Default")
      (node (ref "H8") (pin "4") (pinfunction "4_4") (pintype "unspecified"))
      (node (ref "U1") (pin "11") (pinfunction "P26_11") (pintype "unspecified"))
    )
    (net (code "170") (name "P28") (class "Default")
      (node (ref "H7") (pin "5") (pinfunction "5_5") (pintype "unspecified"))
      (node (ref "U1") (pin "17") (pinfunction "P28_17") (pintype "unspecified"))
    )
    (net (code "171") (name "RST") (class "Default")
      (node (ref "C10") (pin "2") (pinfunction "2_2") (pintype "input"))
      (node (ref "H7") (pin "4") (pinfunction "4_4") (pintype "unspecified"))
      (node (ref "R3") (pin "1") (pinfunction "1_1") (pintype "unspecified"))
      (node (ref "SW5") (pin "2") (pinfunction "2_2") (pintype "input"))
      (node (ref "U1") (pin "18") (pinfunction "CEN_18") (pintype "unspecified"))
    )
    (net (code "172") (name "RX1") (class "Default")
      (node (ref "H7") (pin "6") (pinfunction "6_6") (pintype "unspecified"))
      (node (ref "U1") (pin "16") (pinfunction "RX1_16") (pintype "unspecified"))
    )
    (net (code "173") (name "RX2") (class "Default")
      (node (ref "H6") (pin "6") (pinfunction "6_6") (pintype "unspecified"))
      (node (ref "U1") (pin "6") (pinfunction "RX2_6") (pintype "unspecified"))
    )
    (net (code "174") (name "TX1") (class "Default")
      (node (ref "H7") (pin "7") (pinfunction "7_7") (pintype "unspecified"))
      (node (ref "U1") (pin "15") (pinfunction "TX1_15") (pintype "unspecified"))
    )
    (net (code "175") (name "TX2") (class "Default")
      (node (ref "H6") (pin "7") (pinfunction "7_7") (pintype "unspecified"))
      (node (ref "U1") (pin "7") (pinfunction "TX2_7") (pintype "unspecified"))
    )
    (net (code "176") (name "VCC") (class "Default")
      (node (ref "SW2") (pin "2") (pinfunction "2_2") (pintype "unspecified"))
      (node (ref "USB") (pin "1") (pinfunction "VBUS_1") (pintype "unspecified"))
    )
    (net (code "177") (name "VDD") (class "Default")
      (node (ref "CN1") (pin "1") (pinfunction "1_1") (pintype "unspecified"))
      (node (ref "CN6") (pin "1") (pinfunction "1_1") (pintype "unspecified"))
      (node (ref "L1") (pin "1") (pinfunction "VDD_1") (pintype "unspecified"))
      (node (ref "L10") (pin "1") (pinfunction "VDD_1") (pintype "unspecified"))
      (node (ref "L100") (pin "1") (pinfunction "VDD_1") (pintype "unspecified"))
      (node (ref "L101") (pin "1") (pinfunction "VDD_1") (pintype "unspecified"))
      (node (ref "L102") (pin "1") (pinfunction "VDD_1") (pintype "unspecified"))
      (node (ref "L103") (pin "1") (pinfunction "VDD_1") (pintype "unspecified"))
      (node (ref "L104") (pin "1") (pinfunction "VDD_1") (pintype "unspecified"))
      (node (ref "L105") (pin "1") (pinfunction "VDD_1") (pintype "unspecified"))
      (node (ref "L106") (pin "1") (pinfunction "VDD_1") (pintype "unspecified"))
      (node (ref "L107") (pin "1") (pinfunction "VDD_1") (pintype "unspecified"))
      (node (ref "L108") (pin "1") (pinfunction "VDD_1") (pintype "unspecified"))
      (node (ref "L109") (pin "1") (pinfunction "VDD_1") (pintype "unspecified"))
      (node (ref "L11") (pin "1") (pinfunction "VDD_1") (pintype "unspecified"))
      (node (ref "L110") (pin "1") (pinfunction "VDD_1") (pintype "unspecified"))
      (node (ref "L111") (pin "1") (pinfunction "VDD_1") (pintype "unspecified"))
      (node (ref "L112") (pin "1") (pinfunction "VDD_1") (pintype "unspecified"))
      (node (ref "L113") (pin "1") (pinfunction "VDD_1") (pintype "unspecified"))
      (node (ref "L114") (pin "1") (pinfunction "VDD_1") (pintype "unspecified"))
      (node (ref "L115") (pin "1") (pinfunction "VDD_1") (pintype "unspecified"))
      (node (ref "L116") (pin "1") (pinfunction "VDD_1") (pintype "unspecified"))
      (node (ref "L117") (pin "1") (pinfunction "VDD_1") (pintype "unspecified"))
      (node (ref "L118") (pin "1") (pinfunction "VDD_1") (pintype "unspecified"))
      (node (ref "L119") (pin "1") (pinfunction "VDD_1") (pintype "unspecified"))
      (node (ref "L12") (pin "1") (pinfunction "VDD_1") (pintype "unspecified"))
      (node (ref "L120") (pin "1") (pinfunction "VDD_1") (pintype "unspecified"))
      (node (ref "L121") (pin "1") (pinfunction "VDD_1") (pintype "unspecified"))
      (node (ref "L122") (pin "1") (pinfunction "VDD_1") (pintype "unspecified"))
      (node (ref "L123") (pin "1") (pinfunction "VDD_1") (pintype "unspecified"))
      (node (ref "L124") (pin "1") (pinfunction "VDD_1") (pintype "unspecified"))
      (node (ref "L125") (pin "1") (pinfunction "VDD_1") (pintype "unspecified"))
      (node (ref "L126") (pin "1") (pinfunction "VDD_1") (pintype "unspecified"))
      (node (ref "L127") (pin "1") (pinfunction "VDD_1") (pintype "unspecified"))
      (node (ref "L128") (pin "1") (pinfunction "VDD_1") (pintype "unspecified"))
      (node (ref "L13") (pin "1") (pinfunction "VDD_1") (pintype "unspecified"))
      (node (ref "L14") (pin "1") (pinfunction "VDD_1") (pintype "unspecified"))
      (node (ref "L15") (pin "1") (pinfunction "VDD_1") (pintype "unspecified"))
      (node (ref "L16") (pin "1") (pinfunction "VDD_1") (pintype "unspecified"))
      (node (ref "L17") (pin "1") (pinfunction "VDD_1") (pintype "unspecified"))
      (node (ref "L18") (pin "1") (pinfunction "VDD_1") (pintype "unspecified"))
      (node (ref "L19") (pin "1") (pinfunction "VDD_1") (pintype "unspecified"))
      (node (ref "L2") (pin "1") (pinfunction "VDD_1") (pintype "unspecified"))
      (node (ref "L20") (pin "1") (pinfunction "VDD_1") (pintype "unspecified"))
      (node (ref "L21") (pin "1") (pinfunction "VDD_1") (pintype "unspecified"))
      (node (ref "L22") (pin "1") (pinfunction "VDD_1") (pintype "unspecified"))
      (node (ref "L23") (pin "1") (pinfunction "VDD_1") (pintype "unspecified"))
      (node (ref "L24") (pin "1") (pinfunction "VDD_1") (pintype "unspecified"))
      (node (ref "L25") (pin "1") (pinfunction "VDD_1") (pintype "unspecified"))
      (node (ref "L26") (pin "1") (pinfunction "VDD_1") (pintype "unspecified"))
      (node (ref "L27") (pin "1") (pinfunction "VDD_1") (pintype "unspecified"))
      (node (ref "L28") (pin "1") (pinfunction "VDD_1") (pintype "unspecified"))
      (node (ref "L29") (pin "1") (pinfunction "VDD_1") (pintype "unspecified"))
      (node (ref "L3") (pin "1") (pinfunction "VDD_1") (pintype "unspecified"))
      (node (ref "L30") (pin "1") (pinfunction "VDD_1") (pintype "unspecified"))
      (node (ref "L31") (pin "1") (pinfunction "VDD_1") (pintype "unspecified"))
      (node (ref "L32") (pin "1") (pinfunction "VDD_1") (pintype "unspecified"))
      (node (ref "L33") (pin "1") (pinfunction "VDD_1") (pintype "unspecified"))
      (node (ref "L34") (pin "1") (pinfunction "VDD_1") (pintype "unspecified"))
      (node (ref "L35") (pin "1") (pinfunction "VDD_1") (pintype "unspecified"))
      (node (ref "L36") (pin "1") (pinfunction "VDD_1") (pintype "unspecified"))
      (node (ref "L37") (pin "1") (pinfunction "VDD_1") (pintype "unspecified"))
      (node (ref "L38") (pin "1") (pinfunction "VDD_1") (pintype "unspecified"))
      (node (ref "L39") (pin "1") (pinfunction "VDD_1") (pintype "unspecified"))
      (node (ref "L4") (pin "1") (pinfunction "VDD_1") (pintype "unspecified"))
      (node (ref "L40") (pin "1") (pinfunction "VDD_1") (pintype "unspecified"))
      (node (ref "L41") (pin "1") (pinfunction "VDD_1") (pintype "unspecified"))
      (node (ref "L42") (pin "1") (pinfunction "VDD_1") (pintype "unspecified"))
      (node (ref "L43") (pin "1") (pinfunction "VDD_1") (pintype "unspecified"))
      (node (ref "L44") (pin "1") (pinfunction "VDD_1") (pintype "unspecified"))
      (node (ref "L45") (pin "1") (pinfunction "VDD_1") (pintype "unspecified"))
      (node (ref "L46") (pin "1") (pinfunction "VDD_1") (pintype "unspecified"))
      (node (ref "L47") (pin "1") (pinfunction "VDD_1") (pintype "unspecified"))
      (node (ref "L48") (pin "1") (pinfunction "VDD_1") (pintype "unspecified"))
      (node (ref "L49") (pin "1") (pinfunction "VDD_1") (pintype "unspecified"))
      (node (ref "L5") (pin "1") (pinfunction "VDD_1") (pintype "unspecified"))
      (node (ref "L50") (pin "1") (pinfunction "VDD_1") (pintype "unspecified"))
      (node (ref "L51") (pin "1") (pinfunction "VDD_1") (pintype "unspecified"))
      (node (ref "L52") (pin "1") (pinfunction "VDD_1") (pintype "unspecified"))
      (node (ref "L53") (pin "1") (pinfunction "VDD_1") (pintype "unspecified"))
      (node (ref "L54") (pin "1") (pinfunction "VDD_1") (pintype "unspecified"))
      (node (ref "L55") (pin "1") (pinfunction "VDD_1") (pintype "unspecified"))
      (node (ref "L56") (pin "1") (pinfunction "VDD_1") (pintype "unspecified"))
      (node (ref "L57") (pin "1") (pinfunction "VDD_1") (pintype "unspecified"))
      (node (ref "L58") (pin "1") (pinfunction "VDD_1") (pintype "unspecified"))
      (node (ref "L59") (pin "1") (pinfunction "VDD_1") (pintype "unspecified"))
      (node (ref "L6") (pin "1") (pinfunction "VDD_1") (pintype "unspecified"))
      (node (ref "L60") (pin "1") (pinfunction "VDD_1") (pintype "unspecified"))
      (node (ref "L61") (pin "1") (pinfunction "VDD_1") (pintype "unspecified"))
      (node (ref "L62") (pin "1") (pinfunction "VDD_1") (pintype "unspecified"))
      (node (ref "L63") (pin "1") (pinfunction "VDD_1") (pintype "unspecified"))
      (node (ref "L64") (pin "1") (pinfunction "VDD_1") (pintype "unspecified"))
      (node (ref "L65") (pin "1") (pinfunction "VDD_1") (pintype "unspecified"))
      (node (ref "L66") (pin "1") (pinfunction "VDD_1") (pintype "unspecified"))
      (node (ref "L67") (pin "1") (pinfunction "VDD_1") (pintype "unspecified"))
      (node (ref "L68") (pin "1") (pinfunction "VDD_1") (pintype "unspecified"))
      (node (ref "L69") (pin "1") (pinfunction "VDD_1") (pintype "unspecified"))
      (node (ref "L7") (pin "1") (pinfunction "VDD_1") (pintype "unspecified"))
      (node (ref "L70") (pin "1") (pinfunction "VDD_1") (pintype "unspecified"))
      (node (ref "L71") (pin "1") (pinfunction "VDD_1") (pintype "unspecified"))
      (node (ref "L72") (pin "1") (pinfunction "VDD_1") (pintype "unspecified"))
      (node (ref "L73") (pin "1") (pinfunction "VDD_1") (pintype "unspecified"))
      (node (ref "L74") (pin "1") (pinfunction "VDD_1") (pintype "unspecified"))
      (node (ref "L75") (pin "1") (pinfunction "VDD_1") (pintype "unspecified"))
      (node (ref "L76") (pin "1") (pinfunction "VDD_1") (pintype "unspecified"))
      (node (ref "L77") (pin "1") (pinfunction "VDD_1") (pintype "unspecified"))
      (node (ref "L78") (pin "1") (pinfunction "VDD_1") (pintype "unspecified"))
      (node (ref "L79") (pin "1") (pinfunction "VDD_1") (pintype "unspecified"))
      (node (ref "L8") (pin "1") (pinfunction "VDD_1") (pintype "unspecified"))
      (node (ref "L80") (pin "1") (pinfunction "VDD_1") (pintype "unspecified"))
      (node (ref "L81") (pin "1") (pinfunction "VDD_1") (pintype "unspecified"))
      (node (ref "L82") (pin "1") (pinfunction "VDD_1") (pintype "unspecified"))
      (node (ref "L83") (pin "1") (pinfunction "VDD_1") (pintype "unspecified"))
      (node (ref "L84") (pin "1") (pinfunction "VDD_1") (pintype "unspecified"))
      (node (ref "L85") (pin "1") (pinfunction "VDD_1") (pintype "unspecified"))
      (node (ref "L86") (pin "1") (pinfunction "VDD_1") (pintype "unspecified"))
      (node (ref "L87") (pin "1") (pinfunction "VDD_1") (pintype "unspecified"))
      (node (ref "L88") (pin "1") (pinfunction "VDD_1") (pintype "unspecified"))
      (node (ref "L89") (pin "1") (pinfunction "VDD_1") (pintype "unspecified"))
      (node (ref "L9") (pin "1") (pinfunction "VDD_1") (pintype "unspecified"))
      (node (ref "L90") (pin "1") (pinfunction "VDD_1") (pintype "unspecified"))
      (node (ref "L91") (pin "1") (pinfunction "VDD_1") (pintype "unspecified"))
      (node (ref "L92") (pin "1") (pinfunction "VDD_1") (pintype "unspecified"))
      (node (ref "L93") (pin "1") (pinfunction "VDD_1") (pintype "unspecified"))
      (node (ref "L94") (pin "1") (pinfunction "VDD_1") (pintype "unspecified"))
      (node (ref "L95") (pin "1") (pinfunction "VDD_1") (pintype "unspecified"))
      (node (ref "L96") (pin "1") (pinfunction "VDD_1") (pintype "unspecified"))
      (node (ref "L97") (pin "1") (pinfunction "VDD_1") (pintype "unspecified"))
      (node (ref "L98") (pin "1") (pinfunction "VDD_1") (pintype "unspecified"))
      (node (ref "L99") (pin "1") (pinfunction "VDD_1") (pintype "unspecified"))
    )
    (net (code "178") (name "unconnected-(L128-DOUT-Pad2)") (class "Default")
      (node (ref "L128") (pin "2") (pinfunction "DOUT_2") (pintype "unspecified+no_connect"))
    )
    (net (code "179") (name "unconnected-(M5-Pad1)") (class "Default")
      (node (ref "M5") (pin "1") (pinfunction "1_1") (pintype "unspecified+no_connect"))
    )
    (net (code "180") (name "unconnected-(M6-Pad1)") (class "Default")
      (node (ref "M6") (pin "1") (pinfunction "1_1") (pintype "unspecified+no_connect"))
    )
    (net (code "181") (name "unconnected-(M7-Pad1)") (class "Default")
      (node (ref "M7") (pin "1") (pinfunction "1_1") (pintype "unspecified+no_connect"))
    )
    (net (code "182") (name "unconnected-(M8-Pad1)") (class "Default")
      (node (ref "M8") (pin "1") (pinfunction "1_1") (pintype "unspecified+no_connect"))
    )
    (net (code "183") (name "unconnected-(SW2-Pad1)") (class "Default")
      (node (ref "SW2") (pin "1") (pinfunction "1_1") (pintype "unspecified+no_connect"))
    )
    (net (code "184") (name "unconnected-(USB-D+-Pad3)") (class "Default")
      (node (ref "USB") (pin "3") (pinfunction "D+_3") (pintype "unspecified+no_connect"))
    )
    (net (code "185") (name "unconnected-(USB-D--Pad2)") (class "Default")
      (node (ref "USB") (pin "2") (pinfunction "D-_2") (pintype "unspecified+no_connect"))
    )
    (net (code "186") (name "unconnected-(USB-ID-Pad4)") (class "Default")
      (node (ref "USB") (pin "4") (pinfunction "ID_4") (pintype "unspecified+no_connect"))
    )
  )
)
